# MD016A.net
KiCad netlist of a schematic drawn in Altium Designer
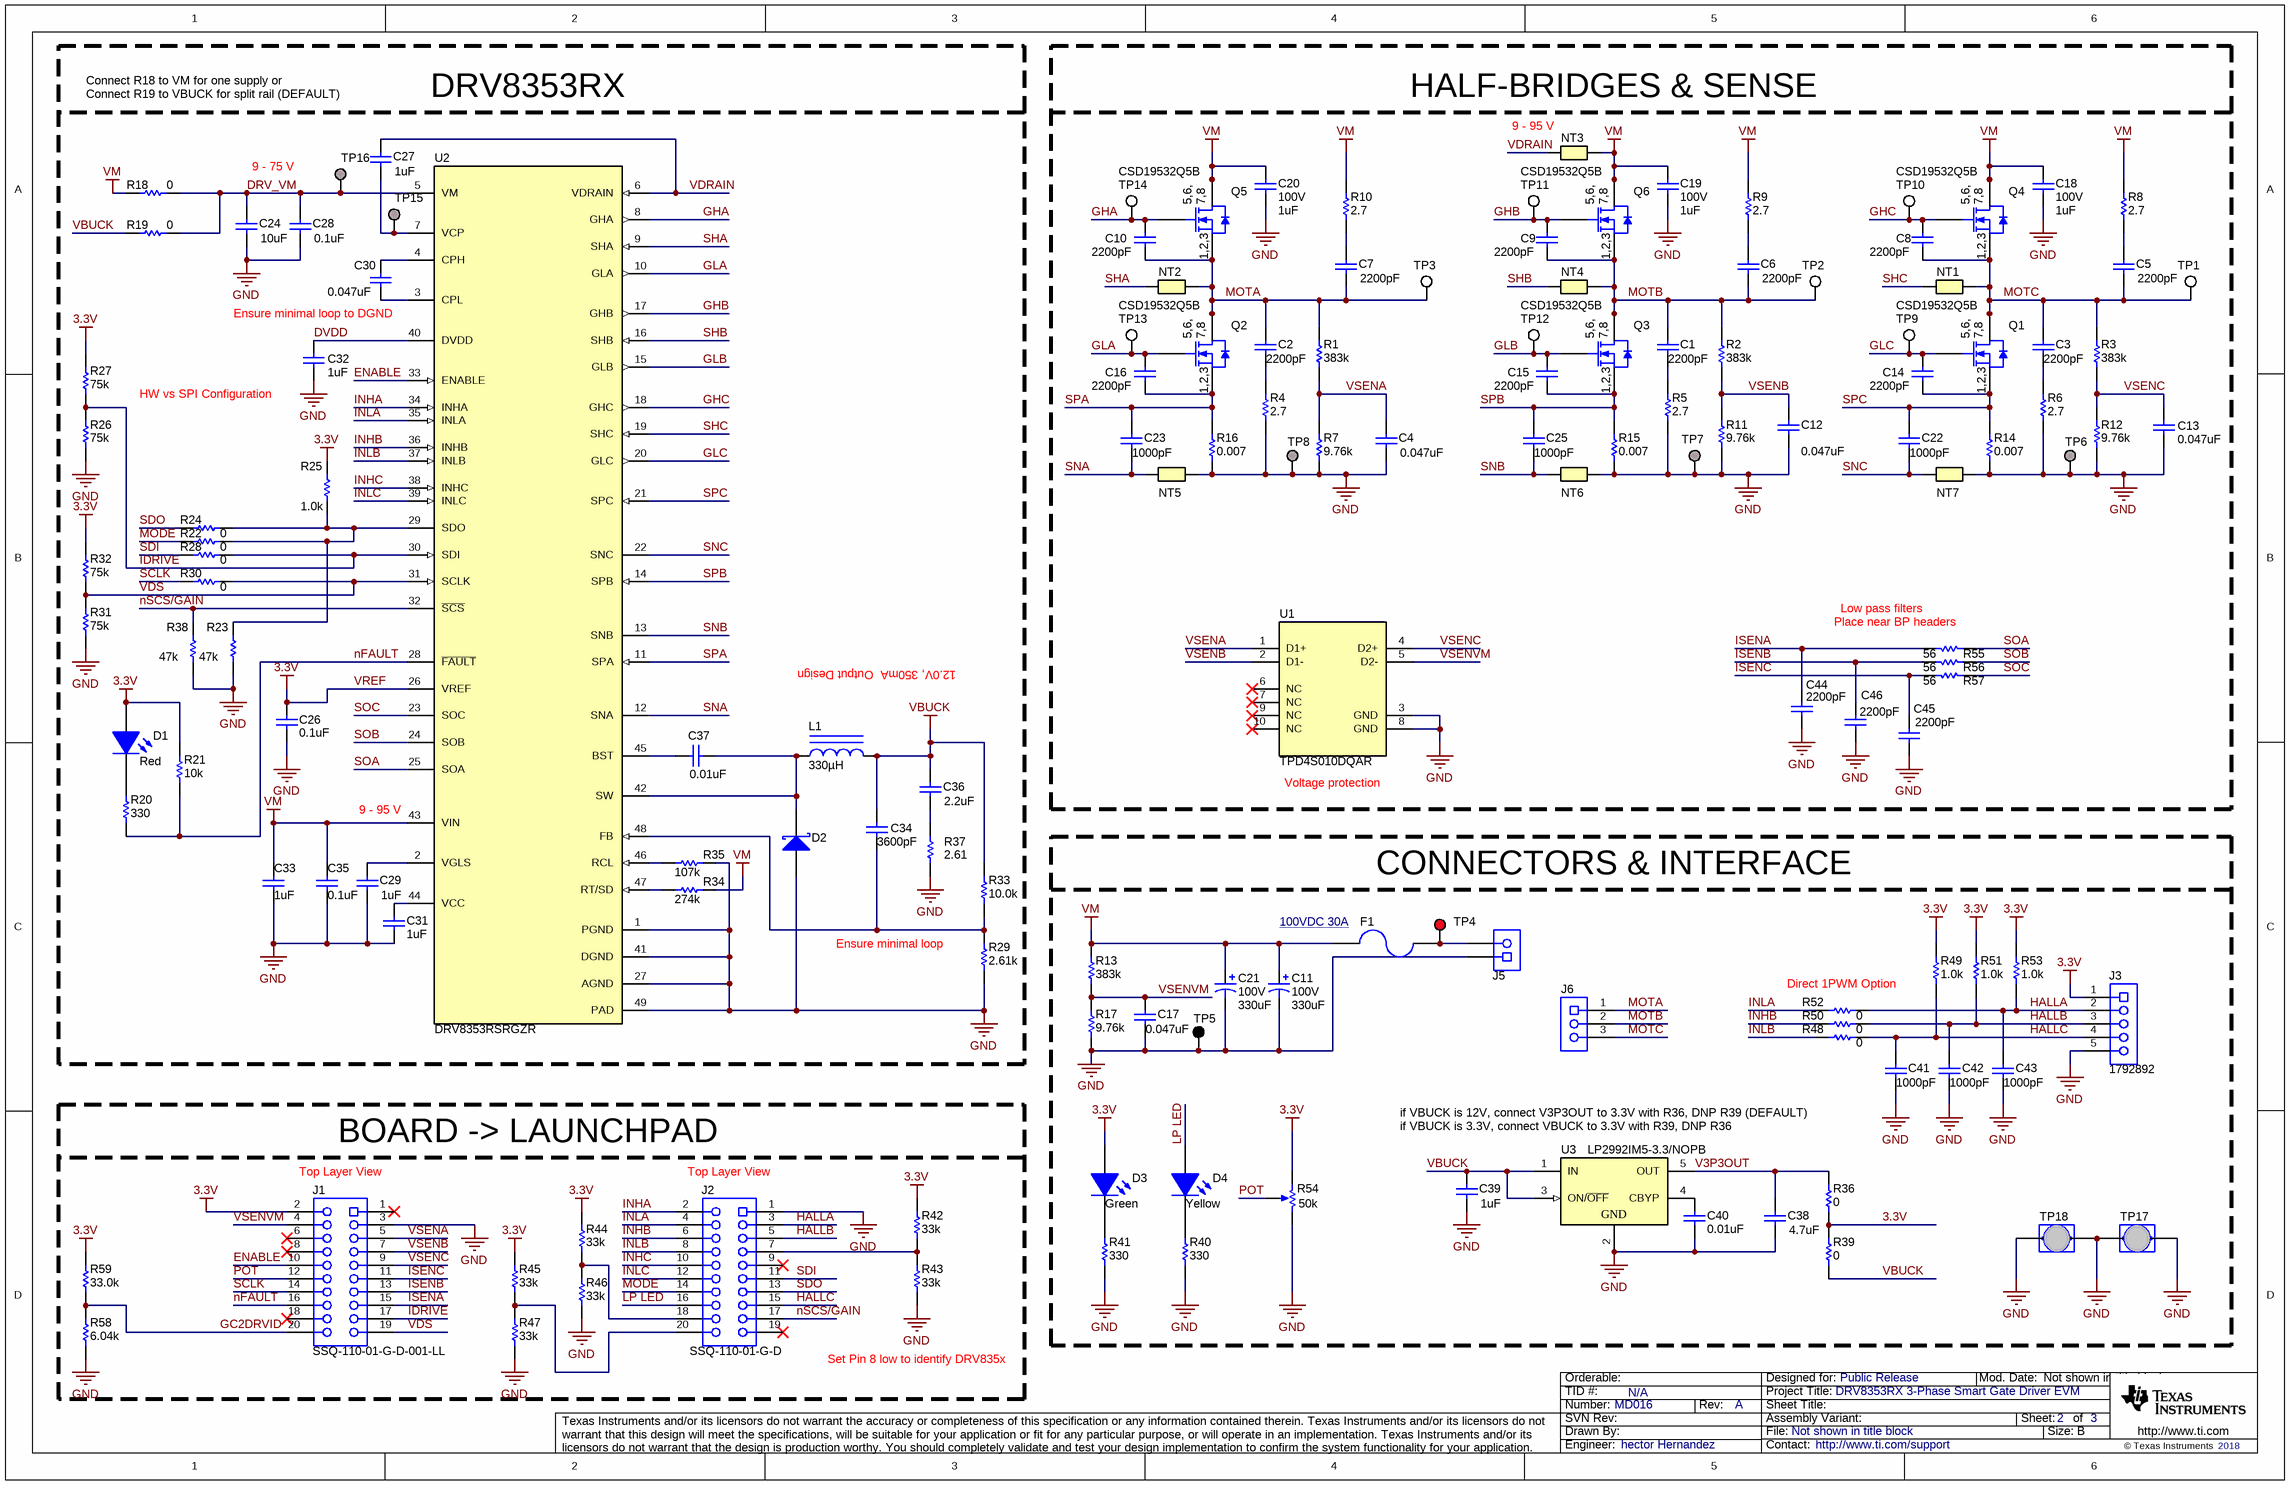
[diagram p0: MD016A.SchDoc]

(export (version "E")
  (design (tool "Eeschema 10.0.6"))
  (components
    (comp (ref "C1")
      (value "GRM188R72A222KA01D")
      (footprint "0603_HV")
      (description "CAP, CERM, 2200 pF, 100 V, +/- 10%, X7R, 0603")
      (fields
        (field (name "MANUFACTURER") "MuRata")
        (field (name "VALUEDISPLAYED") "2200pF")
        (field (name "PUBLISHER") "Texas Instruments")
      )
      (libsource (lib "Altium Vault - TI") (part "CMP-0007475-4"))
    )
    (comp (ref "C2")
      (value "GRM188R72A222KA01D")
      (footprint "0603_HV")
      (description "CAP, CERM, 2200 pF, 100 V, +/- 10%, X7R, 0603")
      (fields
        (field (name "MANUFACTURER") "MuRata")
        (field (name "VALUEDISPLAYED") "2200pF")
        (field (name "PUBLISHER") "Texas Instruments")
      )
      (libsource (lib "Altium Vault - TI") (part "CMP-0007475-4"))
    )
    (comp (ref "C3")
      (value "GRM188R72A222KA01D")
      (footprint "0603_HV")
      (description "CAP, CERM, 2200 pF, 100 V, +/- 10%, X7R, 0603")
      (fields
        (field (name "MANUFACTURER") "MuRata")
        (field (name "VALUEDISPLAYED") "2200pF")
        (field (name "PUBLISHER") "Texas Instruments")
      )
      (libsource (lib "Altium Vault - TI") (part "CMP-0007475-4"))
    )
    (comp (ref "C4")
      (value "06033C473JAT2A")
      (footprint "0603L")
      (description "CAP, CERM, 0.047 uF, 25 V, +/- 5%, X7R, 0603")
      (fields
        (field (name "MANUFACTURER") "AVX")
        (field (name "VALUEDISPLAYED") "0.047uF")
        (field (name "PUBLISHER") "Texas Instruments")
      )
      (libsource (lib "Altium Vault - TI") (part "CMP-0006757-5"))
    )
    (comp (ref "C5")
      (value "GRM188R72A222KA01D")
      (footprint "0603_HV")
      (description "CAP, CERM, 2200 pF, 100 V, +/- 10%, X7R, 0603")
      (fields
        (field (name "MANUFACTURER") "MuRata")
        (field (name "VALUEDISPLAYED") "2200pF")
        (field (name "PUBLISHER") "Texas Instruments")
      )
      (libsource (lib "Altium Vault - TI") (part "CMP-0007475-4"))
    )
    (comp (ref "C6")
      (value "GRM188R72A222KA01D")
      (footprint "0603_HV")
      (description "CAP, CERM, 2200 pF, 100 V, +/- 10%, X7R, 0603")
      (fields
        (field (name "MANUFACTURER") "MuRata")
        (field (name "VALUEDISPLAYED") "2200pF")
        (field (name "PUBLISHER") "Texas Instruments")
      )
      (libsource (lib "Altium Vault - TI") (part "CMP-0007475-4"))
    )
    (comp (ref "C7")
      (value "GRM188R72A222KA01D")
      (footprint "0603_HV")
      (description "CAP, CERM, 2200 pF, 100 V, +/- 10%, X7R, 0603")
      (fields
        (field (name "MANUFACTURER") "MuRata")
        (field (name "VALUEDISPLAYED") "2200pF")
        (field (name "PUBLISHER") "Texas Instruments")
      )
      (libsource (lib "Altium Vault - TI") (part "CMP-0007475-4"))
    )
    (comp (ref "C8")
      (value "06031C222KAT2A")
      (footprint "0603_HV")
      (description "CAP, CERM, 2200 pF, 100 V, +/- 10%, X7R, 0603")
      (fields
        (field (name "MANUFACTURER") "AVX")
        (field (name "VALUEDISPLAYED") "2200pF")
        (field (name "PUBLISHER") "Texas Instruments")
      )
      (libsource (lib "Altium Vault - TI") (part "CMP-0006737-4"))
    )
    (comp (ref "C9")
      (value "06031C222KAT2A")
      (footprint "0603_HV")
      (description "CAP, CERM, 2200 pF, 100 V, +/- 10%, X7R, 0603")
      (fields
        (field (name "MANUFACTURER") "AVX")
        (field (name "VALUEDISPLAYED") "2200pF")
        (field (name "PUBLISHER") "Texas Instruments")
      )
      (libsource (lib "Altium Vault - TI") (part "CMP-0006737-4"))
    )
    (comp (ref "C10")
      (value "06031C222KAT2A")
      (footprint "0603_HV")
      (description "CAP, CERM, 2200 pF, 100 V, +/- 10%, X7R, 0603")
      (fields
        (field (name "MANUFACTURER") "AVX")
        (field (name "VALUEDISPLAYED") "2200pF")
        (field (name "PUBLISHER") "Texas Instruments")
      )
      (libsource (lib "Altium Vault - TI") (part "CMP-0006737-4"))
    )
    (comp (ref "C11")
      (value "EEV-FK2A331M")
      (footprint "SM_RADIAL_K16")
      (description "CAP, AL, 330 uF, 100 V, +/- 20%, 0.153 ohm, AEC-Q200 Grade 2, SMD")
      (fields
        (field (name "MANUFACTURER") "Panasonic")
        (field (name "VDC_V") "100V")
        (field (name "VALUEDISPLAYED") "330uF")
        (field (name "PUBLISHER") "Texas Instruments")
      )
      (libsource (lib "Altium Vault - TI") (part "Cap_Polarized"))
    )
    (comp (ref "C12")
      (value "06033C473JAT2A")
      (footprint "0603L")
      (description "CAP, CERM, 0.047 uF, 25 V, +/- 5%, X7R, 0603")
      (fields
        (field (name "MANUFACTURER") "AVX")
        (field (name "VALUEDISPLAYED") "0.047uF")
        (field (name "PUBLISHER") "Texas Instruments")
      )
      (libsource (lib "Altium Vault - TI") (part "CMP-0006757-5"))
    )
    (comp (ref "C13")
      (value "06033C473JAT2A")
      (footprint "0603L")
      (description "CAP, CERM, 0.047 uF, 25 V, +/- 5%, X7R, 0603")
      (fields
        (field (name "MANUFACTURER") "AVX")
        (field (name "VALUEDISPLAYED") "0.047uF")
        (field (name "PUBLISHER") "Texas Instruments")
      )
      (libsource (lib "Altium Vault - TI") (part "CMP-0006757-5"))
    )
    (comp (ref "C14")
      (value "06031C222KAT2A")
      (footprint "0603_HV")
      (description "CAP, CERM, 2200 pF, 100 V, +/- 10%, X7R, 0603")
      (fields
        (field (name "MANUFACTURER") "AVX")
        (field (name "VALUEDISPLAYED") "2200pF")
        (field (name "PUBLISHER") "Texas Instruments")
      )
      (libsource (lib "Altium Vault - TI") (part "CMP-0006737-4"))
    )
    (comp (ref "C15")
      (value "06031C222KAT2A")
      (footprint "0603_HV")
      (description "CAP, CERM, 2200 pF, 100 V, +/- 10%, X7R, 0603")
      (fields
        (field (name "MANUFACTURER") "AVX")
        (field (name "VALUEDISPLAYED") "2200pF")
        (field (name "PUBLISHER") "Texas Instruments")
      )
      (libsource (lib "Altium Vault - TI") (part "CMP-0006737-4"))
    )
    (comp (ref "C16")
      (value "06031C222KAT2A")
      (footprint "0603_HV")
      (description "CAP, CERM, 2200 pF, 100 V, +/- 10%, X7R, 0603")
      (fields
        (field (name "MANUFACTURER") "AVX")
        (field (name "VALUEDISPLAYED") "2200pF")
        (field (name "PUBLISHER") "Texas Instruments")
      )
      (libsource (lib "Altium Vault - TI") (part "CMP-0006737-4"))
    )
    (comp (ref "C17")
      (value "06033C473JAT2A")
      (footprint "0603L")
      (description "CAP, CERM, 0.047 uF, 25 V, +/- 5%, X7R, 0603")
      (fields
        (field (name "MANUFACTURER") "AVX")
        (field (name "VALUEDISPLAYED") "0.047uF")
        (field (name "PUBLISHER") "Texas Instruments")
      )
      (libsource (lib "Altium Vault - TI") (part "CMP-0006757-5"))
    )
    (comp (ref "C18")
      (value "CL31B105KCHNNNE")
      (footprint "1206_180M")
      (description "CAP, CERM, 1 uF, 100 V, +/- 10%, X7R, 1206")
      (fields
        (field (name "MANUFACTURER") "Samsung")
        (field (name "VDC_V") "100V")
        (field (name "VALUEDISPLAYED") "1uF")
        (field (name "PUBLISHER") "Texas Instruments")
      )
      (libsource (lib "Altium Vault - TI") (part "CMP-0008801-2"))
    )
    (comp (ref "C19")
      (value "CL31B105KCHNNNE")
      (footprint "1206_180M")
      (description "CAP, CERM, 1 uF, 100 V, +/- 10%, X7R, 1206")
      (fields
        (field (name "MANUFACTURER") "Samsung")
        (field (name "VDC_V") "100V")
        (field (name "VALUEDISPLAYED") "1uF")
        (field (name "PUBLISHER") "Texas Instruments")
      )
      (libsource (lib "Altium Vault - TI") (part "CMP-0008801-2"))
    )
    (comp (ref "C20")
      (value "CL31B105KCHNNNE")
      (footprint "1206_180M")
      (description "CAP, CERM, 1 uF, 100 V, +/- 10%, X7R, 1206")
      (fields
        (field (name "MANUFACTURER") "Samsung")
        (field (name "VDC_V") "100V")
        (field (name "VALUEDISPLAYED") "1uF")
        (field (name "PUBLISHER") "Texas Instruments")
      )
      (libsource (lib "Altium Vault - TI") (part "CMP-0008801-2"))
    )
    (comp (ref "C21")
      (value "EEV-FK2A331M")
      (footprint "SM_RADIAL_K16")
      (description "CAP, AL, 330 uF, 100 V, +/- 20%, 0.153 ohm, AEC-Q200 Grade 2, SMD")
      (fields
        (field (name "MANUFACTURER") "Panasonic")
        (field (name "VDC_V") "100V")
        (field (name "VALUEDISPLAYED") "330uF")
        (field (name "PUBLISHER") "Texas Instruments")
      )
      (libsource (lib "Altium Vault - TI") (part "CMP-0011224-2"))
    )
    (comp (ref "C22")
      (value "885012206034")
      (footprint "0603L")
      (description "CAP, CERM, 1000 pF, 16 V, +/- 10%, X7R, 0603")
      (fields
        (field (name "MANUFACTURER") "Wurth Elektronik")
        (field (name "VALUEDISPLAYED") "1000pF")
        (field (name "PUBLISHER") "Texas Instruments")
      )
      (libsource (lib "Altium Vault - TI") (part "CMP-0006826-4"))
    )
    (comp (ref "C23")
      (value "885012206034")
      (footprint "0603L")
      (description "CAP, CERM, 1000 pF, 16 V, +/- 10%, X7R, 0603")
      (fields
        (field (name "MANUFACTURER") "Wurth Elektronik")
        (field (name "VALUEDISPLAYED") "1000pF")
        (field (name "PUBLISHER") "Texas Instruments")
      )
      (libsource (lib "Altium Vault - TI") (part "CMP-0006826-4"))
    )
    (comp (ref "C24")
      (value "CGA9N3X7S2A106K230KE")
      (footprint "2220_280M")
      (description "CAP, CERM, 10 uF, 100 V,+/- 10%, X7S, AEC-Q200 Grade 1, 2220")
      (fields
        (field (name "MANUFACTURER") "TDK")
        (field (name "VALUEDISPLAYED") "10uF")
        (field (name "PUBLISHER") "Texas Instruments")
      )
      (libsource (lib "Altium Vault - TI") (part "CMP-0064964-2"))
    )
    (comp (ref "C25")
      (value "885012206034")
      (footprint "0603L")
      (description "CAP, CERM, 1000 pF, 16 V, +/- 10%, X7R, 0603")
      (fields
        (field (name "MANUFACTURER") "Wurth Elektronik")
        (field (name "VALUEDISPLAYED") "1000pF")
        (field (name "PUBLISHER") "Texas Instruments")
      )
      (libsource (lib "Altium Vault - TI") (part "CMP-0006826-4"))
    )
    (comp (ref "C26")
      (value "C0603C104J4RACTU")
      (footprint "0603L")
      (description "CAP, CERM, 0.1 uF, 16 V, +/- 5%, X7R, 0603")
      (fields
        (field (name "VALUEDISPLAYED") "0.1uF")
        (field (name "MANUFACTURER") "Kemet")
        (field (name "PUBLISHER") "Texas Instruments")
      )
      (libsource (lib "Altium Vault - TI") (part "CMP-0006857-4"))
    )
    (comp (ref "C27")
      (value "CL31B105KCHNNNE")
      (footprint "1206_180M")
      (description "CAP, CERM, 1 uF, 100 V, +/- 10%, X7R, 1206")
      (fields
        (field (name "MANUFACTURER") "Samsung")
        (field (name "VALUEDISPLAYED") "1uF")
        (field (name "PUBLISHER") "Texas Instruments")
      )
      (libsource (lib "Altium Vault - TI") (part "CMP-0008801-2"))
    )
    (comp (ref "C28")
      (value "C2012X7R2A104K125AA")
      (footprint "0805_HV")
      (description "CAP, CERM, 0.1 uF, 100 V, +/- 10%, X7R, 0805")
      (fields
        (field (name "MANUFACTURER") "TDK")
        (field (name "VALUEDISPLAYED") "0.1uF")
        (field (name "PUBLISHER") "Texas Instruments")
      )
      (libsource (lib "Altium Vault - TI") (part "CMP-0007886-2"))
    )
    (comp (ref "C29")
      (value "C1608X7R1C105K080AC")
      (footprint "0603L")
      (description "CAP, CERM, 1 uF, 16 V, +/- 10%, X7R, 0603")
      (fields
        (field (name "MANUFACTURER") "TDK")
        (field (name "VALUEDISPLAYED") "1uF")
        (field (name "PUBLISHER") "Texas Instruments")
      )
      (libsource (lib "Altium Vault - TI") (part "CMP-0007037-4"))
    )
    (comp (ref "C30")
      (value "C2012X7R2A473K125AA")
      (footprint "0805_HV")
      (description "CAP, CERM, 0.047 uF, 100 V, +/- 10%, X7R, 0805")
      (fields
        (field (name "VALUEDISPLAYED") "0.047uF")
        (field (name "MANUFACTURER") "TDK")
        (field (name "PUBLISHER") "Texas Instruments")
      )
      (libsource (lib "Altium Vault - TI") (part "CMP-0007887-2"))
    )
    (comp (ref "C31")
      (value "C1608X7R1C105K080AC")
      (footprint "0603L")
      (description "CAP, CERM, 1 uF, 16 V, +/- 10%, X7R, 0603")
      (fields
        (field (name "MANUFACTURER") "TDK")
        (field (name "VALUEDISPLAYED") "1uF")
        (field (name "PUBLISHER") "Texas Instruments")
      )
      (libsource (lib "Altium Vault - TI") (part "CMP-0007037-4"))
    )
    (comp (ref "C32")
      (value "EMK107B7105KA-T")
      (footprint "0603L")
      (description "CAP, CERM, 1 uF, 16 V, +/- 10%, X7R, 0603")
      (fields
        (field (name "MANUFACTURER") "Taiyo Yuden")
        (field (name "VALUEDISPLAYED") "1uF")
        (field (name "PUBLISHER") "Texas Instruments")
      )
      (libsource (lib "Altium Vault - TI") (part "CMP-0007120-4"))
    )
    (comp (ref "C33")
      (value "CL31B105KCHNNNE")
      (footprint "1206_180M")
      (description "CAP, CERM, 1 uF, 100 V, +/- 10%, X7R, 1206")
      (fields
        (field (name "MANUFACTURER") "Samsung")
        (field (name "VALUEDISPLAYED") "1uF")
        (field (name "PUBLISHER") "Texas Instruments")
      )
      (libsource (lib "Altium Vault - TI") (part "CMP-0008801-2"))
    )
    (comp (ref "C34")
      (value "GRM1885C1H362JA01D")
      (footprint "0603L")
      (description "CAP, CERM, 3600 pF, 50 V, +/- 5%, C0G/NP0, 0603")
      (fields
        (field (name "MANUFACTURER") "MuRata")
        (field (name "VALUEDISPLAYED") "3600pF")
        (field (name "PUBLISHER") "Texas Instruments")
      )
      (libsource (lib "Altium Vault - TI") (part "CMP-0007213-4"))
    )
    (comp (ref "C35")
      (value "C2012X7R2A104K125AA")
      (footprint "0805_HV")
      (description "CAP, CERM, 0.1 uF, 100 V, +/- 10%, X7R, 0805")
      (fields
        (field (name "MANUFACTURER") "TDK")
        (field (name "VALUEDISPLAYED") "0.1uF")
        (field (name "PUBLISHER") "Texas Instruments")
      )
      (libsource (lib "Altium Vault - TI") (part "CMP-0007886-2"))
    )
    (comp (ref "C36")
      (value "C2012X7R1V225K085AC")
      (footprint "0805L")
      (description "CAP, CERM, 2.2 uF, 35 V, +/- 10%, X7R, 0805")
      (fields
        (field (name "MANUFACTURER") "TDK")
        (field (name "VALUEDISPLAYED") "2.2uF")
        (field (name "PUBLISHER") "Texas Instruments")
      )
      (libsource (lib "Altium Vault - TI") (part "CMP-0007883-2"))
    )
    (comp (ref "C37")
      (value "C0603C103K4RACTU")
      (footprint "0603L")
      (description "CAP, CERM, 0.01 uF, 16 V, +/- 10%, X7R, 0603")
      (fields
        (field (name "MANUFACTURER") "Kemet")
        (field (name "VALUEDISPLAYED") "0.01uF")
        (field (name "PUBLISHER") "Texas Instruments")
      )
      (libsource (lib "Altium Vault - TI") (part "CMP-0006853-4"))
    )
    (comp (ref "C38")
      (value "GRM32ER71K475KE14L")
      (footprint "1210_270L")
      (description "CAP, CERM, 4.7 uF, 80 V, +/- 10%, X7R, 1210")
      (fields
        (field (name "MANUFACTURER") "MuRata")
        (field (name "VALUEDISPLAYED") "4.7uF")
        (field (name "PUBLISHER") "Texas Instruments")
      )
      (libsource (lib "Altium Vault - TI") (part "CMP-0009230-2"))
    )
    (comp (ref "C39")
      (value "CL21B105KBFNNNE")
      (footprint "0805L")
      (description "CAP, CERM, 1 uF, 50 V, +/- 10%, X7R, 0805")
      (fields
        (field (name "MANUFACTURER") "Samsung Electro-Mechanics")
        (field (name "VALUEDISPLAYED") "1uF")
        (field (name "PUBLISHER") "Texas Instruments")
      )
      (libsource (lib "Altium Vault - TI") (part "CMP-0007994-2"))
    )
    (comp (ref "C40")
      (value "C0603C103K4RACTU")
      (footprint "0603L")
      (description "CAP, CERM, 0.01 uF, 16 V, +/- 10%, X7R, 0603")
      (fields
        (field (name "VALUEDISPLAYED") "0.01uF")
        (field (name "MANUFACTURER") "Kemet")
        (field (name "PUBLISHER") "Texas Instruments")
      )
      (libsource (lib "Altium Vault - TI") (part "Capacitor"))
    )
    (comp (ref "C41")
      (value "885012206034")
      (footprint "0603L")
      (description "CAP, CERM, 1000 pF, 16 V, +/- 10%, X7R, 0603")
      (fields
        (field (name "MANUFACTURER") "Wurth Elektronik")
        (field (name "VALUEDISPLAYED") "1000pF")
        (field (name "PUBLISHER") "Texas Instruments")
      )
      (libsource (lib "Altium Vault - TI") (part "CMP-0006826-4"))
    )
    (comp (ref "C42")
      (value "885012206034")
      (footprint "0603L")
      (description "CAP, CERM, 1000 pF, 16 V, +/- 10%, X7R, 0603")
      (fields
        (field (name "MANUFACTURER") "Wurth Elektronik")
        (field (name "VALUEDISPLAYED") "1000pF")
        (field (name "PUBLISHER") "Texas Instruments")
      )
      (libsource (lib "Altium Vault - TI") (part "CMP-0006826-4"))
    )
    (comp (ref "C43")
      (value "885012206034")
      (footprint "0603L")
      (description "CAP, CERM, 1000 pF, 16 V, +/- 10%, X7R, 0603")
      (fields
        (field (name "MANUFACTURER") "Wurth Elektronik")
        (field (name "VALUEDISPLAYED") "1000pF")
        (field (name "PUBLISHER") "Texas Instruments")
      )
      (libsource (lib "Altium Vault - TI") (part "CMP-0006826-4"))
    )
    (comp (ref "C44")
      (value "GRM188R71C222KA01D")
      (footprint "0603L")
      (description "CAP, CERM, 2200 pF, 16 V, +/- 10%, X7R, 0603")
      (fields
        (field (name "VALUEDISPLAYED") "2200pF")
        (field (name "MANUFACTURER") "MuRata")
        (field (name "PUBLISHER") "Texas Instruments")
      )
      (libsource (lib "Altium Vault - TI") (part "Capacitor"))
    )
    (comp (ref "C45")
      (value "GRM188R71C222KA01D")
      (footprint "0603L")
      (description "CAP, CERM, 2200 pF, 16 V, +/- 10%, X7R, 0603")
      (fields
        (field (name "VALUEDISPLAYED") "2200pF")
        (field (name "MANUFACTURER") "MuRata")
        (field (name "PUBLISHER") "Texas Instruments")
      )
      (libsource (lib "Altium Vault - TI") (part "Capacitor"))
    )
    (comp (ref "C46")
      (value "GRM188R71C222KA01D")
      (footprint "0603L")
      (description "CAP, CERM, 2200 pF, 16 V, +/- 10%, X7R, 0603")
      (fields
        (field (name "VALUEDISPLAYED") "2200pF")
        (field (name "MANUFACTURER") "MuRata")
        (field (name "PUBLISHER") "Texas Instruments")
      )
      (libsource (lib "Altium Vault - TI") (part "Capacitor"))
    )
    (comp (ref "D1")
      (value "Red")
      (footprint "LED_LTST-C170_Red")
      (description "LED, Red, SMD")
      (fields
        (field (name "MANUFACTURER") "Lite-On")
        (field (name "PARTNUMBER") "LTST-C170KRKT")
        (field (name "PUBLISHER") "Texas Instruments")
      )
      (libsource (lib "Altium Vault - TI") (part "LED"))
    )
    (comp (ref "D2")
      (value "DFLS1200-7")
      (footprint "PowerDI123")
      (description "Diode, Schottky, 200 V, 1 A, PowerDI123")
      (fields (field (name "MANUFACTURER") "Diodes Inc.") (field (name "PUBLISHER") "Texas Instruments"))
      (libsource (lib "Altium Vault - TI") (part "DIODE_SCHOTTKY"))
    )
    (comp (ref "D3")
      (value "Green")
      (footprint "LTST-C170KGKT_Green")
      (description "LED, Green, SMD")
      (fields
        (field (name "MANUFACTURER") "Lite-On")
        (field (name "PARTNUMBER") "LTST-C170KGKT")
        (field (name "PUBLISHER") "Texas Instruments")
      )
      (libsource (lib "Altium Vault - TI") (part "LED"))
    )
    (comp (ref "D4")
      (value "Yellow")
      (footprint "LED_LTST-C170")
      (description "LED, Yellow , SMD")
      (fields
        (field (name "MANUFACTURER") "Lite-On")
        (field (name "PARTNUMBER") "LTST-C170KSKT")
        (field (name "PUBLISHER") "Texas Instruments")
      )
      (libsource (lib "Altium Vault - TI") (part "LED"))
    )
    (comp (ref "F1")
      (value "100VDC 30A")
      (footprint "Fuse_0463")
      (description "Fuse, 30 A, 250 VAC, 100 VDC, SMD")
      (fields (field (name "PARTNUMBER") "0463030.ER") (field (name "MANUFACTURER") "Littelfuse"))
      (libsource (lib "Altium Vault - TI") (part "CMP-0077200-3"))
    )
    (comp (ref "J1")
      (value "SSQ-110-01-G-D-001-LL")
      (footprint "Samtec_SSQ-110-01-x-D-001-LL")
      (description "Receptacle, 2.54mm, 10x2, Gold, TH")
      (fields (field (name "MANUFACTURER") "Samtec"))
      (libsource (lib "Altium Vault - TI") (part "Receptacle_10x2"))
    )
    (comp (ref "J2")
      (value "SSQ-110-01-G-D")
      (footprint "Samtec_SSQ-110-01-x-D")
      (description "Receptacle, 2.54mm, 10x2, Gold, TH")
      (fields (field (name "MANUFACTURER") "Samtec"))
      (libsource (lib "Altium Vault - TI") (part "CMP-0082605-1"))
    )
    (comp (ref "J3")
      (value "1792892")
      (footprint "Phoenix_1792892")
      (description "Terminal Block, 5mm, 5x1, R/A, TH")
      (fields (field (name "MANUFACTURER") "Phoenix Contact") (field (name "PUBLISHER") "Texas Instruments"))
      (libsource (lib "Altium Vault - TI") (part "Receptacle_5x1"))
    )
    (comp (ref "J5")
      (value "1902547")
      (footprint "Phoenix_1902547")
      (description "Terminal Block, 9.52mm, 2x1, R/A, TH")
      (fields (field (name "MANUFACTURER") "Phoenix Contact") (field (name "PUBLISHER") "Texas Instruments"))
      (libsource (lib "Altium Vault - TI") (part "CMP-0055527-1"))
    )
    (comp (ref "J6")
      (value "1904150")
      (footprint "Phoenix_1904150")
      (description "Terminal Block, 9.52mm, 3x1, R/A, TH")
      (fields (field (name "MANUFACTURER") "Phoenix Contact") (field (name "PUBLISHER") "Texas Instruments"))
      (libsource (lib "Altium Vault - TI") (part "Receptacle_3x1"))
    )
    (comp (ref "L1")
      (value "74404084331")
      (footprint "WE-LQS_8040")
      (description "Inductor, Shielded, 330 µH, 0.66 A, 1.1245 ohm, SMD")
      (fields (field (name "MANUFACTURER") "Wurth Elektronik") (field (name "VALUEDISPLAYED") "330µH"))
      (libsource (lib "Altium Vault - TI") (part "Inductor_Iron"))
    )
    (comp (ref "NT1")
      (value "Net-Tie")
      (footprint "Net-Tie_10mil")
      (description "Single point connection between nets.")
      (libsource (lib "Altium Vault - TI") (part "Net-Tie"))
    )
    (comp (ref "NT2")
      (value "Net-Tie")
      (footprint "Net-Tie_10mil")
      (description "Single point connection between nets.")
      (libsource (lib "Altium Vault - TI") (part "Net-Tie"))
    )
    (comp (ref "NT3")
      (value "Net-Tie")
      (footprint "Net-Tie_50milWide_30milLong")
      (description "Single point connection between nets.")
      (libsource (lib "Altium Vault - TI") (part "Net-Tie"))
    )
    (comp (ref "NT4")
      (value "Net-Tie")
      (footprint "Net-Tie_10mil")
      (description "Single point connection between nets.")
      (libsource (lib "Altium Vault - TI") (part "Net-Tie"))
    )
    (comp (ref "NT5")
      (value "Net-Tie")
      (footprint "Net-Tie_10mil")
      (description "Single point connection between nets.")
      (libsource (lib "Altium Vault - TI") (part "Net-Tie"))
    )
    (comp (ref "NT6")
      (value "Net-Tie")
      (footprint "Net-Tie_10mil")
      (description "Single point connection between nets.")
      (libsource (lib "Altium Vault - TI") (part "Net-Tie"))
    )
    (comp (ref "NT7")
      (value "Net-Tie")
      (footprint "Net-Tie_10mil")
      (description "Single point connection between nets.")
      (libsource (lib "Altium Vault - TI") (part "Net-Tie"))
    )
    (comp (ref "Q1")
      (value "CSD19532Q5B")
      (footprint "DNK0008A")
      (description "MOSFET, N-CH, 100 V, 17 A, DNK0008A (VSON-CLIP-8)")
      (fields (field (name "MANUFACTURER") "Texas Instruments"))
      (libsource (lib "Altium Vault - TI") (part "MOSFET_N_D56789G4S123"))
    )
    (comp (ref "Q2")
      (value "CSD19532Q5B")
      (footprint "DNK0008A")
      (description "MOSFET, N-CH, 100 V, 17 A, DNK0008A (VSON-CLIP-8)")
      (fields (field (name "MANUFACTURER") "Texas Instruments"))
      (libsource (lib "Altium Vault - TI") (part "MOSFET_N_D56789G4S123"))
    )
    (comp (ref "Q3")
      (value "CSD19532Q5B")
      (footprint "DNK0008A")
      (description "MOSFET, N-CH, 100 V, 17 A, DNK0008A (VSON-CLIP-8)")
      (fields (field (name "MANUFACTURER") "Texas Instruments"))
      (libsource (lib "Altium Vault - TI") (part "MOSFET_N_D56789G4S123"))
    )
    (comp (ref "Q4")
      (value "CSD19532Q5B")
      (footprint "DNK0008A")
      (description "MOSFET, N-CH, 100 V, 17 A, DNK0008A (VSON-CLIP-8)")
      (fields (field (name "MANUFACTURER") "Texas Instruments"))
      (libsource (lib "Altium Vault - TI") (part "MOSFET_N_D56789G4S123"))
    )
    (comp (ref "Q5")
      (value "CSD19532Q5B")
      (footprint "DNK0008A")
      (description "MOSFET, N-CH, 100 V, 17 A, DNK0008A (VSON-CLIP-8)")
      (fields (field (name "MANUFACTURER") "Texas Instruments"))
      (libsource (lib "Altium Vault - TI") (part "MOSFET_N_D56789G4S123"))
    )
    (comp (ref "Q6")
      (value "CSD19532Q5B")
      (footprint "DNK0008A")
      (description "MOSFET, N-CH, 100 V, 17 A, DNK0008A (VSON-CLIP-8)")
      (fields (field (name "MANUFACTURER") "Texas Instruments"))
      (libsource (lib "Altium Vault - TI") (part "MOSFET_N_D56789G4S123"))
    )
    (comp (ref "R1")
      (value "CRCW0603383KFKEA")
      (footprint "0603_HV")
      (description "RES, 383 k, 1%, 0.1 W, AEC-Q200 Grade 0, 0603")
      (fields (field (name "MANUFACTURER") "Vishay-Dale") (field (name "VALUEDISPLAYED") "383k"))
      (libsource (lib "Altium Vault - TI") (part "CMP-0022362-4"))
    )
    (comp (ref "R2")
      (value "CRCW0603383KFKEA")
      (footprint "0603_HV")
      (description "RES, 383 k, 1%, 0.1 W, AEC-Q200 Grade 0, 0603")
      (fields (field (name "MANUFACTURER") "Vishay-Dale") (field (name "VALUEDISPLAYED") "383k"))
      (libsource (lib "Altium Vault - TI") (part "CMP-0022362-4"))
    )
    (comp (ref "R3")
      (value "CRCW0603383KFKEA")
      (footprint "0603_HV")
      (description "RES, 383 k, 1%, 0.1 W, AEC-Q200 Grade 0, 0603")
      (fields (field (name "MANUFACTURER") "Vishay-Dale") (field (name "VALUEDISPLAYED") "383k"))
      (libsource (lib "Altium Vault - TI") (part "CMP-0022362-4"))
    )
    (comp (ref "R4")
      (value "CRCW08052R70JNEA")
      (footprint "0805_HV")
      (description "RES, 2.7, 5%, 0.125 W, 0805")
      (fields
        (field (name "MANUFACTURER") "Vishay-Dale")
        (field (name "VALUEDISPLAYED") "2.7")
        (field (name "PUBLISHER") "Texas Instruments")
      )
      (libsource (lib "Altium Vault - TI") (part "CMP-0020521-2"))
    )
    (comp (ref "R5")
      (value "CRCW08052R70JNEA")
      (footprint "0805_HV")
      (description "RES, 2.7, 5%, 0.125 W, 0805")
      (fields
        (field (name "MANUFACTURER") "Vishay-Dale")
        (field (name "VALUEDISPLAYED") "2.7")
        (field (name "PUBLISHER") "Texas Instruments")
      )
      (libsource (lib "Altium Vault - TI") (part "CMP-0020521-2"))
    )
    (comp (ref "R6")
      (value "CRCW08052R70JNEA")
      (footprint "0805_HV")
      (description "RES, 2.7, 5%, 0.125 W, 0805")
      (fields
        (field (name "MANUFACTURER") "Vishay-Dale")
        (field (name "VALUEDISPLAYED") "2.7")
        (field (name "PUBLISHER") "Texas Instruments")
      )
      (libsource (lib "Altium Vault - TI") (part "CMP-0020521-2"))
    )
    (comp (ref "R7")
      (value "RC0603FR-079K76L")
      (footprint "0603L")
      (description "RES, 9.76 k, 1%, 0.1 W, 0603")
      (fields (field (name "MANUFACTURER") "Yageo") (field (name "VALUEDISPLAYED") "9.76k"))
      (libsource (lib "Altium Vault - TI") (part "CMP-0023336-5"))
    )
    (comp (ref "R8")
      (value "CRCW08052R70JNEA")
      (footprint "0805_HV")
      (description "RES, 2.7, 5%, 0.125 W, 0805")
      (fields
        (field (name "MANUFACTURER") "Vishay-Dale")
        (field (name "VALUEDISPLAYED") "2.7")
        (field (name "PUBLISHER") "Texas Instruments")
      )
      (libsource (lib "Altium Vault - TI") (part "CMP-0020521-2"))
    )
    (comp (ref "R9")
      (value "CRCW08052R70JNEA")
      (footprint "0805_HV")
      (description "RES, 2.7, 5%, 0.125 W, 0805")
      (fields
        (field (name "MANUFACTURER") "Vishay-Dale")
        (field (name "VALUEDISPLAYED") "2.7")
        (field (name "PUBLISHER") "Texas Instruments")
      )
      (libsource (lib "Altium Vault - TI") (part "CMP-0020521-2"))
    )
    (comp (ref "R10")
      (value "CRCW08052R70JNEA")
      (footprint "0805_HV")
      (description "RES, 2.7, 5%, 0.125 W, 0805")
      (fields
        (field (name "MANUFACTURER") "Vishay-Dale")
        (field (name "VALUEDISPLAYED") "2.7")
        (field (name "PUBLISHER") "Texas Instruments")
      )
      (libsource (lib "Altium Vault - TI") (part "CMP-0020521-2"))
    )
    (comp (ref "R11")
      (value "RC0603FR-079K76L")
      (footprint "0603L")
      (description "RES, 9.76 k, 1%, 0.1 W, 0603")
      (fields (field (name "MANUFACTURER") "Yageo") (field (name "VALUEDISPLAYED") "9.76k"))
      (libsource (lib "Altium Vault - TI") (part "CMP-0023336-5"))
    )
    (comp (ref "R12")
      (value "RC0603FR-079K76L")
      (footprint "0603L")
      (description "RES, 9.76 k, 1%, 0.1 W, 0603")
      (fields (field (name "MANUFACTURER") "Yageo") (field (name "VALUEDISPLAYED") "9.76k"))
      (libsource (lib "Altium Vault - TI") (part "CMP-0023336-5"))
    )
    (comp (ref "R13")
      (value "CRCW0603383KFKEA")
      (footprint "0603_HV")
      (description "RES, 383 k, 1%, 0.1 W, AEC-Q200 Grade 0, 0603")
      (fields (field (name "MANUFACTURER") "Vishay-Dale") (field (name "VALUEDISPLAYED") "383k"))
      (libsource (lib "Altium Vault - TI") (part "CMP-0022362-4"))
    )
    (comp (ref "R14")
      (value "CRE2512-FZ-R007E-3")
      (footprint "CRE2512-R5_R9")
      (description "RES, 0.007, 1%, 3 W, AEC-Q200 Grade 0, 2512")
      (fields
        (field (name "VALUEDISPLAYED") "0.007")
        (field (name "MANUFACTURER") "Bourns")
        (field (name "PUBLISHER") "Texas Instruments")
      )
      (libsource (lib "Altium Vault - TI") (part "Resistor"))
    )
    (comp (ref "R15")
      (value "CRE2512-FZ-R007E-3")
      (footprint "CRE2512-R5_R9")
      (description "RES, 0.007, 1%, 3 W, AEC-Q200 Grade 0, 2512")
      (fields
        (field (name "VALUEDISPLAYED") "0.007")
        (field (name "MANUFACTURER") "Bourns")
        (field (name "PUBLISHER") "Texas Instruments")
      )
      (libsource (lib "Altium Vault - TI") (part "Resistor"))
    )
    (comp (ref "R16")
      (value "CRE2512-FZ-R007E-3")
      (footprint "CRE2512-R5_R9")
      (description "RES, 0.007, 1%, 3 W, AEC-Q200 Grade 0, 2512")
      (fields
        (field (name "VALUEDISPLAYED") "0.007")
        (field (name "MANUFACTURER") "Bourns")
        (field (name "PUBLISHER") "Texas Instruments")
      )
      (libsource (lib "Altium Vault - TI") (part "Resistor"))
    )
    (comp (ref "R17")
      (value "RC0603FR-079K76L")
      (footprint "0603L")
      (description "RES, 9.76 k, 1%, 0.1 W, 0603")
      (fields (field (name "MANUFACTURER") "Yageo") (field (name "VALUEDISPLAYED") "9.76k"))
      (libsource (lib "Altium Vault - TI") (part "CMP-0023336-5"))
    )
    (comp (ref "R18")
      (value "RC1206JR-070RL")
      (footprint "1206")
      (description "RES, 0, 5%, 0.25 W, 1206")
      (fields
        (field (name "MANUFACTURER") "Yageo America")
        (field (name "VALUEDISPLAYED") "0")
        (field (name "PUBLISHER") "Texas Instruments")
      )
      (libsource (lib "Altium Vault - TI") (part "Resistor"))
    )
    (comp (ref "R19")
      (value "RC1206JR-070RL")
      (footprint "1206")
      (description "RES, 0, 5%, 0.25 W, 1206")
      (fields
        (field (name "MANUFACTURER") "Yageo America")
        (field (name "VALUEDISPLAYED") "0")
        (field (name "PUBLISHER") "Texas Instruments")
      )
      (libsource (lib "Altium Vault - TI") (part "Resistor"))
    )
    (comp (ref "R20")
      (value "CRCW0603330RJNEA")
      (footprint "0603L")
      (description "RES, 330, 5%, 0.1 W, AEC-Q200 Grade 0, 0603")
      (fields (field (name "MANUFACTURER") "Vishay-Dale") (field (name "VALUEDISPLAYED") "330"))
      (libsource (lib "Altium Vault - TI") (part "CMP-0025785-4"))
    )
    (comp (ref "R21")
      (value "RC0603JR-0710KL")
      (footprint "0603L")
      (description "RES, 10 k, 5%, 0.1 W, 0603")
      (fields
        (field (name "MANUFACTURER") "Yageo America")
        (field (name "VALUEDISPLAYED") "10k")
        (field (name "PUBLISHER") "Texas Instruments")
      )
      (libsource (lib "Altium Vault - TI") (part "CMP-0025886-3"))
    )
    (comp (ref "R22")
      (value "ERJ-3GEY0R00V")
      (footprint "0603L")
      (description "RES, 0, 5%, 0.1 W, 0603")
      (fields
        (field (name "MANUFACTURER") "Panasonic")
        (field (name "VALUEDISPLAYED") "0")
        (field (name "PUBLISHER") "Texas Instruments")
      )
      (libsource (lib "Altium Vault - TI") (part "CMP-0025874-3"))
    )
    (comp (ref "R23")
      (value "CRCW060347K0JNEA")
      (footprint "0603L")
      (description "RES, 47 k, 5%, 0.1 W, AEC-Q200 Grade 0, 0603")
      (fields (field (name "VALUEDISPLAYED") "47k") (field (name "MANUFACTURER") "Vishay-Dale"))
      (libsource (lib "Altium Vault - TI") (part "CMP-0025814-4"))
    )
    (comp (ref "R24")
      (value "ERJ-3GEY0R00V")
      (footprint "0603L")
      (description "RES, 0, 5%, 0.1 W, 0603")
      (fields
        (field (name "MANUFACTURER") "Panasonic")
        (field (name "VALUEDISPLAYED") "0")
        (field (name "PUBLISHER") "Texas Instruments")
      )
      (libsource (lib "Altium Vault - TI") (part "CMP-0025874-3"))
    )
    (comp (ref "R25")
      (value "RCA06031K00JNEA")
      (footprint "0603L")
      (description "RES, 1.0 k, 5%, 0.1 W, AEC-Q200 Grade 0, 0603")
      (fields
        (field (name "MANUFACTURER") "Vishay-Dale")
        (field (name "VALUEDISPLAYED") "1.0k")
        (field (name "PUBLISHER") "Texas Instruments")
      )
      (libsource (lib "Altium Vault - TI") (part "CMP-0025946-3"))
    )
    (comp (ref "R26")
      (value "CRCW060375K0JNEA")
      (footprint "0603L")
      (description "RES, 75 k, 5%, 0.1 W, AEC-Q200 Grade 0, 0603")
      (fields (field (name "VALUEDISPLAYED") "75k") (field (name "MANUFACTURER") "Vishay-Dale"))
      (libsource (lib "Altium Vault - TI") (part "CMP-0025853-4"))
    )
    (comp (ref "R27")
      (value "CRCW060375K0JNEA")
      (footprint "0603L")
      (description "RES, 75 k, 5%, 0.1 W, AEC-Q200 Grade 0, 0603")
      (fields (field (name "VALUEDISPLAYED") "75k") (field (name "MANUFACTURER") "Vishay-Dale"))
      (libsource (lib "Altium Vault - TI") (part "CMP-0025853-4"))
    )
    (comp (ref "R28")
      (value "ERJ-3GEY0R00V")
      (footprint "0603L")
      (description "RES, 0, 5%, 0.1 W, 0603")
      (fields
        (field (name "MANUFACTURER") "Panasonic")
        (field (name "VALUEDISPLAYED") "0")
        (field (name "PUBLISHER") "Texas Instruments")
      )
      (libsource (lib "Altium Vault - TI") (part "CMP-0025874-3"))
    )
    (comp (ref "R29")
      (value "RG1608P-2611-B-T5")
      (footprint "0603L")
      (description "RES, 2.61 k, 0.1%, 0.1 W, 0603")
      (fields
        (field (name "MANUFACTURER") "Susumu Co Ltd")
        (field (name "VALUEDISPLAYED") "2.61k")
        (field (name "PUBLISHER") "Texas Instruments")
      )
      (libsource (lib "Altium Vault - TI") (part "CMP-0023494-3"))
    )
    (comp (ref "R30")
      (value "ERJ-3GEY0R00V")
      (footprint "0603L")
      (description "RES, 0, 5%, 0.1 W, 0603")
      (fields
        (field (name "MANUFACTURER") "Panasonic")
        (field (name "VALUEDISPLAYED") "0")
        (field (name "PUBLISHER") "Texas Instruments")
      )
      (libsource (lib "Altium Vault - TI") (part "CMP-0025874-3"))
    )
    (comp (ref "R31")
      (value "CRCW060375K0JNEA")
      (footprint "0603L")
      (description "RES, 75 k, 5%, 0.1 W, AEC-Q200 Grade 0, 0603")
      (fields (field (name "VALUEDISPLAYED") "75k") (field (name "MANUFACTURER") "Vishay-Dale"))
      (libsource (lib "Altium Vault - TI") (part "CMP-0025853-4"))
    )
    (comp (ref "R32")
      (value "CRCW060375K0JNEA")
      (footprint "0603L")
      (description "RES, 75 k, 5%, 0.1 W, AEC-Q200 Grade 0, 0603")
      (fields (field (name "VALUEDISPLAYED") "75k") (field (name "MANUFACTURER") "Vishay-Dale"))
      (libsource (lib "Altium Vault - TI") (part "CMP-0025853-4"))
    )
    (comp (ref "R33")
      (value "RG1608P-103-B-T5")
      (footprint "0603L")
      (description "RES, 10.0 k, 0.1%, 0.1 W, 0603")
      (fields
        (field (name "MANUFACTURER") "Susumu Co Ltd")
        (field (name "VALUEDISPLAYED") "10.0k")
        (field (name "PUBLISHER") "Texas Instruments")
      )
      (libsource (lib "Altium Vault - TI") (part "CMP-0023404-3"))
    )
    (comp (ref "R34")
      (value "RC0603FR-07274KL")
      (footprint "0603_HV")
      (description "RES, 274 k, 1%, 0.1 W, 0603")
      (fields
        (field (name "MANUFACTURER") "Yageo America")
        (field (name "VALUEDISPLAYED") "274k")
        (field (name "PUBLISHER") "Texas Instruments")
      )
      (libsource (lib "Altium Vault - TI") (part "CMP-0022963-2"))
    )
    (comp (ref "R35")
      (value "RC0603FR-07107KL")
      (footprint "0603L")
      (description "RES, 107 k, 1%, 0.1 W, 0603")
      (fields
        (field (name "MANUFACTURER") "Yageo America")
        (field (name "VALUEDISPLAYED") "107k")
        (field (name "PUBLISHER") "Texas Instruments")
      )
      (libsource (lib "Altium Vault - TI") (part "CMP-0022741-2"))
    )
    (comp (ref "R36")
      (value "ERJ-3GEY0R00V")
      (footprint "0603L")
      (description "RES, 0, 5%, 0.1 W, 0603")
      (fields
        (field (name "MANUFACTURER") "Panasonic")
        (field (name "VALUEDISPLAYED") "0")
        (field (name "PUBLISHER") "Texas Instruments")
      )
      (libsource (lib "Altium Vault - TI") (part "CMP-0025874-3"))
    )
    (comp (ref "R37")
      (value "CRCW06032R61FKEA")
      (footprint "0603L")
      (description "RES, 2.61, 1%, 0.1 W, AEC-Q200 Grade 0, 0603")
      (fields (field (name "MANUFACTURER") "Vishay-Dale") (field (name "VALUEDISPLAYED") "2.61"))
      (libsource (lib "Altium Vault - TI") (part "CMP-0022313-4"))
    )
    (comp (ref "R38")
      (value "CRCW060347K0JNEA")
      (footprint "0603L")
      (description "RES, 47 k, 5%, 0.1 W, AEC-Q200 Grade 0, 0603")
      (fields (field (name "VALUEDISPLAYED") "47k") (field (name "MANUFACTURER") "Vishay-Dale"))
      (libsource (lib "Altium Vault - TI") (part "CMP-0025814-4"))
    )
    (comp (ref "R39")
      (value "ERJ-3GEY0R00V")
      (footprint "0603L")
      (description "RES, 0, 5%, 0.1 W, 0603")
      (fields
        (field (name "MANUFACTURER") "Panasonic")
        (field (name "VALUEDISPLAYED") "0")
        (field (name "PUBLISHER") "Texas Instruments")
      )
      (libsource (lib "Altium Vault - TI") (part "CMP-0025874-3"))
    )
    (comp (ref "R40")
      (value "CRCW0603330RJNEA")
      (footprint "0603L")
      (description "RES, 330, 5%, 0.1 W, AEC-Q200 Grade 0, 0603")
      (fields (field (name "MANUFACTURER") "Vishay-Dale") (field (name "VALUEDISPLAYED") "330"))
      (libsource (lib "Altium Vault - TI") (part "CMP-0025785-4"))
    )
    (comp (ref "R41")
      (value "CRCW0603330RJNEA")
      (footprint "0603L")
      (description "RES, 330, 5%, 0.1 W, AEC-Q200 Grade 0, 0603")
      (fields (field (name "MANUFACTURER") "Vishay-Dale") (field (name "VALUEDISPLAYED") "330"))
      (libsource (lib "Altium Vault - TI") (part "CMP-0025785-4"))
    )
    (comp (ref "R42")
      (value "Resistor")
      (footprint "0603L")
      (description "RES, 33 k, 5%, 0.1 W, AEC-Q200 Grade 0, 0603")
      (fields
        (field (name "PARTNUMBER") "CRCW060333K0JNEA")
        (field (name "VALUEDISPLAYED") "33k")
        (field (name "MANUFACTURER") "Vishay-Dale")
      )
      (libsource (lib "Altium Vault - TI") (part "CMP-0025786-4"))
    )
    (comp (ref "R43")
      (value "Resistor")
      (footprint "0603L")
      (description "RES, 33 k, 5%, 0.1 W, AEC-Q200 Grade 0, 0603")
      (fields
        (field (name "PARTNUMBER") "CRCW060333K0JNEA")
        (field (name "VALUEDISPLAYED") "33k")
        (field (name "MANUFACTURER") "Vishay-Dale")
      )
      (libsource (lib "Altium Vault - TI") (part "CMP-0025786-4"))
    )
    (comp (ref "R44")
      (value "Resistor")
      (footprint "0603L")
      (description "RES, 33 k, 5%, 0.1 W, AEC-Q200 Grade 0, 0603")
      (fields
        (field (name "PARTNUMBER") "CRCW060333K0JNEA")
        (field (name "VALUEDISPLAYED") "33k")
        (field (name "MANUFACTURER") "Vishay-Dale")
      )
      (libsource (lib "Altium Vault - TI") (part "Resistor"))
    )
    (comp (ref "R45")
      (value "Resistor")
      (footprint "0603L")
      (description "RES, 33 k, 5%, 0.1 W, AEC-Q200 Grade 0, 0603")
      (fields
        (field (name "PARTNUMBER") "CRCW060333K0JNEA")
        (field (name "VALUEDISPLAYED") "33k")
        (field (name "MANUFACTURER") "Vishay-Dale")
      )
      (libsource (lib "Altium Vault - TI") (part "Resistor"))
    )
    (comp (ref "R46")
      (value "Resistor")
      (footprint "0603L")
      (description "RES, 33 k, 5%, 0.1 W, AEC-Q200 Grade 0, 0603")
      (fields
        (field (name "PARTNUMBER") "CRCW060333K0JNEA")
        (field (name "VALUEDISPLAYED") "33k")
        (field (name "MANUFACTURER") "Vishay-Dale")
      )
      (libsource (lib "Altium Vault - TI") (part "Resistor"))
    )
    (comp (ref "R47")
      (value "Resistor")
      (footprint "0603L")
      (description "RES, 33 k, 5%, 0.1 W, AEC-Q200 Grade 0, 0603")
      (fields
        (field (name "PARTNUMBER") "CRCW060333K0JNEA")
        (field (name "VALUEDISPLAYED") "33k")
        (field (name "MANUFACTURER") "Vishay-Dale")
      )
      (libsource (lib "Altium Vault - TI") (part "Resistor"))
    )
    (comp (ref "R48")
      (value "ERJ-3GEY0R00V")
      (footprint "0603L")
      (description "RES, 0, 5%, 0.1 W, 0603")
      (fields
        (field (name "MANUFACTURER") "Panasonic")
        (field (name "VALUEDISPLAYED") "0")
        (field (name "PUBLISHER") "Texas Instruments")
      )
      (libsource (lib "Altium Vault - TI") (part "CMP-0025874-3"))
    )
    (comp (ref "R49")
      (value "RCA06031K00JNEA")
      (footprint "0603L")
      (description "RES, 1.0 k, 5%, 0.1 W, AEC-Q200 Grade 0, 0603")
      (fields
        (field (name "MANUFACTURER") "Vishay-Dale")
        (field (name "VALUEDISPLAYED") "1.0k")
        (field (name "PUBLISHER") "Texas Instruments")
      )
      (libsource (lib "Altium Vault - TI") (part "CMP-0025946-3"))
    )
    (comp (ref "R50")
      (value "ERJ-3GEY0R00V")
      (footprint "0603L")
      (description "RES, 0, 5%, 0.1 W, 0603")
      (fields
        (field (name "MANUFACTURER") "Panasonic")
        (field (name "VALUEDISPLAYED") "0")
        (field (name "PUBLISHER") "Texas Instruments")
      )
      (libsource (lib "Altium Vault - TI") (part "CMP-0025874-3"))
    )
    (comp (ref "R51")
      (value "RCA06031K00JNEA")
      (footprint "0603L")
      (description "RES, 1.0 k, 5%, 0.1 W, AEC-Q200 Grade 0, 0603")
      (fields
        (field (name "MANUFACTURER") "Vishay-Dale")
        (field (name "VALUEDISPLAYED") "1.0k")
        (field (name "PUBLISHER") "Texas Instruments")
      )
      (libsource (lib "Altium Vault - TI") (part "CMP-0025946-3"))
    )
    (comp (ref "R52")
      (value "ERJ-3GEY0R00V")
      (footprint "0603L")
      (description "RES, 0, 5%, 0.1 W, 0603")
      (fields
        (field (name "MANUFACTURER") "Panasonic")
        (field (name "VALUEDISPLAYED") "0")
        (field (name "PUBLISHER") "Texas Instruments")
      )
      (libsource (lib "Altium Vault - TI") (part "CMP-0025874-3"))
    )
    (comp (ref "R53")
      (value "RCA06031K00JNEA")
      (footprint "0603L")
      (description "RES, 1.0 k, 5%, 0.1 W, AEC-Q200 Grade 0, 0603")
      (fields
        (field (name "MANUFACTURER") "Vishay-Dale")
        (field (name "VALUEDISPLAYED") "1.0k")
        (field (name "PUBLISHER") "Texas Instruments")
      )
      (libsource (lib "Altium Vault - TI") (part "CMP-0025946-3"))
    )
    (comp (ref "R54")
      (value "50k")
      (footprint "Bourns_3352T")
      (description "Trimming Potentiometer, 50K, 0.5W, TH")
      (fields
        (field (name "PARTNUMBER") "3352T-1-503LF")
        (field (name "MANUFACTURER") "Bourns")
        (field (name "PUBLISHER") "Texas Instruments")
      )
      (libsource (lib "Altium Vault - TI") (part "Potentiometer"))
    )
    (comp (ref "R55")
      (value "56")
      (footprint "0603L")
      (description "RES, 56, 5%, 0.1 W, AEC-Q200 Grade 0, 0603")
      (fields (field (name "PARTNUMBER") "CRCW060356R0JNEA") (field (name "MANUFACTURER") "Vishay-Dale"))
      (libsource (lib "Altium Vault - TI") (part "Resistor"))
    )
    (comp (ref "R56")
      (value "56")
      (footprint "0603L")
      (description "RES, 56, 5%, 0.1 W, AEC-Q200 Grade 0, 0603")
      (fields (field (name "PARTNUMBER") "CRCW060356R0JNEA") (field (name "MANUFACTURER") "Vishay-Dale"))
      (libsource (lib "Altium Vault - TI") (part "Resistor"))
    )
    (comp (ref "R57")
      (value "56")
      (footprint "0603L")
      (description "RES, 56, 5%, 0.1 W, AEC-Q200 Grade 0, 0603")
      (fields (field (name "PARTNUMBER") "CRCW060356R0JNEA") (field (name "MANUFACTURER") "Vishay-Dale"))
      (libsource (lib "Altium Vault - TI") (part "Resistor"))
    )
    (comp (ref "R58")
      (value "RG1608P-6041-B-T5")
      (footprint "0603L")
      (description "RES, 6.04 k, 0.1%, 0.1 W, 0603")
      (fields
        (field (name "MANUFACTURER") "Susumu Co Ltd")
        (field (name "VALUEDISPLAYED") "6.04k")
        (field (name "PUBLISHER") "Texas Instruments")
      )
      (libsource (lib "Altium Vault - TI") (part "CMP-0023581-3"))
    )
    (comp (ref "R59")
      (value "MCT06030C3302FP500")
      (footprint "0603L")
      (description "RES, 33.0 k, 1%, 0.125 W, 0603")
      (fields
        (field (name "MANUFACTURER") "Vishay/Beyschlag")
        (field (name "VALUEDISPLAYED") "33.0k")
        (field (name "PUBLISHER") "Texas Instruments")
      )
      (libsource (lib "Altium Vault - TI") (part "CMP-0022734-3"))
    )
    (comp (ref "TP1")
      (value "5002")
      (footprint "Keystone5002")
      (description "Test Point, Miniature, White, TH")
      (fields (field (name "MANUFACTURER") "Keystone") (field (name "PUBLISHER") "Texas Instruments"))
      (libsource (lib "Altium Vault - TI") (part "5002"))
    )
    (comp (ref "TP2")
      (value "5002")
      (footprint "Keystone5002")
      (description "Test Point, Miniature, White, TH")
      (fields (field (name "MANUFACTURER") "Keystone") (field (name "PUBLISHER") "Texas Instruments"))
      (libsource (lib "Altium Vault - TI") (part "5002"))
    )
    (comp (ref "TP3")
      (value "5002")
      (footprint "Keystone5002")
      (description "Test Point, Miniature, White, TH")
      (fields (field (name "MANUFACTURER") "Keystone") (field (name "PUBLISHER") "Texas Instruments"))
      (libsource (lib "Altium Vault - TI") (part "5002"))
    )
    (comp (ref "TP4")
      (value "5000")
      (footprint "Keystone5000")
      (description "Test Point, Miniature, Red, TH")
      (fields (field (name "MANUFACTURER") "Keystone") (field (name "PUBLISHER") "Texas Instruments"))
      (libsource (lib "Altium Vault - TI") (part "5000"))
    )
    (comp (ref "TP5")
      (value "5001")
      (footprint "Keystone5001")
      (description "Test Point, Miniature, Black, TH")
      (fields (field (name "MANUFACTURER") "Keystone") (field (name "PUBLISHER") "Texas Instruments"))
      (libsource (lib "Altium Vault - TI") (part "5001"))
    )
    (comp (ref "TP6")
      (value "TP_SM_1MM")
      (footprint "TP_SM_1MM")
      (description "1mm Test Point, SMT")
      (fields (field (name "MANUFACTURER") "Any") (field (name "PUBLISHER") "Texas Instruments"))
      (libsource (lib "Altium Vault - TI") (part "TESTPOINT"))
    )
    (comp (ref "TP7")
      (value "TP_SM_1MM")
      (footprint "TP_SM_1MM")
      (description "1mm Test Point, SMT")
      (fields (field (name "MANUFACTURER") "Any") (field (name "PUBLISHER") "Texas Instruments"))
      (libsource (lib "Altium Vault - TI") (part "TESTPOINT"))
    )
    (comp (ref "TP8")
      (value "TP_SM_1MM")
      (footprint "TP_SM_1MM")
      (description "1mm Test Point, SMT")
      (fields (field (name "MANUFACTURER") "Any") (field (name "PUBLISHER") "Texas Instruments"))
      (libsource (lib "Altium Vault - TI") (part "TESTPOINT"))
    )
    (comp (ref "TP9")
      (value "5002")
      (footprint "Keystone5002")
      (description "Test Point, Miniature, White, TH")
      (fields (field (name "MANUFACTURER") "Keystone") (field (name "PUBLISHER") "Texas Instruments"))
      (libsource (lib "Altium Vault - TI") (part "5002"))
    )
    (comp (ref "TP10")
      (value "5002")
      (footprint "Keystone5002")
      (description "Test Point, Miniature, White, TH")
      (fields (field (name "MANUFACTURER") "Keystone") (field (name "PUBLISHER") "Texas Instruments"))
      (libsource (lib "Altium Vault - TI") (part "5002"))
    )
    (comp (ref "TP11")
      (value "5002")
      (footprint "Keystone5002")
      (description "Test Point, Miniature, White, TH")
      (fields (field (name "MANUFACTURER") "Keystone") (field (name "PUBLISHER") "Texas Instruments"))
      (libsource (lib "Altium Vault - TI") (part "5002"))
    )
    (comp (ref "TP12")
      (value "5002")
      (footprint "Keystone5002")
      (description "Test Point, Miniature, White, TH")
      (fields (field (name "MANUFACTURER") "Keystone") (field (name "PUBLISHER") "Texas Instruments"))
      (libsource (lib "Altium Vault - TI") (part "5002"))
    )
    (comp (ref "TP13")
      (value "5002")
      (footprint "Keystone5002")
      (description "Test Point, Miniature, White, TH")
      (fields (field (name "MANUFACTURER") "Keystone") (field (name "PUBLISHER") "Texas Instruments"))
      (libsource (lib "Altium Vault - TI") (part "5002"))
    )
    (comp (ref "TP14")
      (value "5002")
      (footprint "Keystone5002")
      (description "Test Point, Miniature, White, TH")
      (fields (field (name "MANUFACTURER") "Keystone") (field (name "PUBLISHER") "Texas Instruments"))
      (libsource (lib "Altium Vault - TI") (part "5002"))
    )
    (comp (ref "TP15")
      (value "TP_SM_1MM")
      (footprint "TP_SM_1MM")
      (description "1mm Test Point, SMT")
      (fields (field (name "MANUFACTURER") "Any") (field (name "PUBLISHER") "Texas Instruments"))
      (libsource (lib "Altium Vault - TI") (part "TESTPOINT"))
    )
    (comp (ref "TP16")
      (value "TP_SM_1MM")
      (footprint "TP_SM_1MM")
      (description "1mm Test Point, SMT")
      (fields (field (name "MANUFACTURER") "Any") (field (name "PUBLISHER") "Texas Instruments"))
      (libsource (lib "Altium Vault - TI") (part "TESTPOINT"))
    )
    (comp (ref "TP17")
      (value "D3082-05")
      (footprint "Harwin_D3082-05")
      (description "1mm Uninsulated Shorting Plug, 10.16mm spacing, TH")
      (fields (field (name "MANUFACTURER") "Harwin") (field (name "PUBLISHER") "Texas Instruments"))
      (libsource (lib "Altium Vault - TI") (part "Jumper_2p"))
    )
    (comp (ref "TP18")
      (value "D3082-05")
      (footprint "Harwin_D3082-05")
      (description "1mm Uninsulated Shorting Plug, 10.16mm spacing, TH")
      (fields (field (name "MANUFACTURER") "Harwin") (field (name "PUBLISHER") "Texas Instruments"))
      (libsource (lib "Altium Vault - TI") (part "Jumper_2p"))
    )
    (comp (ref "U1")
      (value "TPD4S010DQAR")
      (footprint "DQA0010A")
      (fields (field (name "MANUFACTURER") "Texas Instruments") (field (name "PARTNUMBER") "TPD4S010DQAR"))
      (libsource (lib "Altium Vault - TI") (part "TI-TPD4S010-SON_DQA-10"))
    )
    (comp (ref "U2")
      (value "DRV8353RSRGZR")
      (footprint "RGZ0048L")
      (description "100-V Three-Phase Smart Gate Driver, RGZ0048L (VQFN-48)")
      (fields
        (field (name "ALTERNATE PARTNUMBER") "DRV8353RSRGZT")
        (field (name "MANUFACTURER") "Texas Instruments")
        (field (name "PUBLISHER") "Texas Instruments")
      )
      (libsource (lib "Altium Vault - TI") (part "CMP-0013782-2"))
    )
    (comp (ref "U3")
      (value "LP2992IM5-3.3/NOPB")
      (footprint "DBV0005A_L")
      (description "Micropower 250 mA Low-Noise Ultra Low-Dropout Regulator, 5-pin SOT-23, Pb-Free")
      (fields (field (name "MANUFACTURER") "Texas Instruments"))
      (libsource (lib "Altium Vault - TI") (part "CMP-0071001-1"))
    )
  )
  (nets
    (net (code "1") (name "/DRV_VM") (class "Default")
      (node (ref "C24") (pin "1") (pinfunction "1_1") (pintype "passive"))
      (node (ref "C28") (pin "1") (pinfunction "1_1") (pintype "passive"))
      (node (ref "R18") (pin "2") (pinfunction "2_2") (pintype "passive"))
      (node (ref "R19") (pin "2") (pinfunction "2_2") (pintype "passive"))
      (node (ref "TP16") (pin "1") (pintype "passive"))
      (node (ref "U2") (pin "5") (pinfunction "VM_5") (pintype "power_in"))
    )
    (net (code "2") (name "/DVDD") (class "Default")
      (node (ref "C32") (pin "1") (pinfunction "1_1") (pintype "passive"))
      (node (ref "U2") (pin "40") (pinfunction "DVDD_40") (pintype "power_in"))
    )
    (net (code "3") (name "/ENABLE") (class "Default")
      (node (ref "J1") (pin "10") (pinfunction "10_10") (pintype "passive"))
      (node (ref "U2") (pin "33") (pinfunction "ENABLE_33") (pintype "input"))
    )
    (net (code "4") (name "/GC2DRVID") (class "Default")
      (node (ref "J1") (pin "20") (pinfunction "20_20") (pintype "passive"))
      (node (ref "R58") (pin "2") (pinfunction "2_2") (pintype "passive"))
      (node (ref "R59") (pin "1") (pinfunction "1_1") (pintype "passive"))
    )
    (net (code "5") (name "/GHA") (class "Default")
      (node (ref "C10") (pin "1") (pinfunction "1_1") (pintype "passive"))
      (node (ref "Q5") (pin "4") (pinfunction "G_4") (pintype "passive"))
      (node (ref "TP14") (pin "1") (pintype "passive"))
      (node (ref "U2") (pin "8") (pinfunction "GHA_8") (pintype "output"))
    )
    (net (code "6") (name "/GHB") (class "Default")
      (node (ref "C9") (pin "1") (pinfunction "1_1") (pintype "passive"))
      (node (ref "Q6") (pin "4") (pinfunction "G_4") (pintype "passive"))
      (node (ref "TP11") (pin "1") (pintype "passive"))
      (node (ref "U2") (pin "17") (pinfunction "GHB_17") (pintype "output"))
    )
    (net (code "7") (name "/GHC") (class "Default")
      (node (ref "C8") (pin "1") (pinfunction "1_1") (pintype "passive"))
      (node (ref "Q4") (pin "4") (pinfunction "G_4") (pintype "passive"))
      (node (ref "TP10") (pin "1") (pintype "passive"))
      (node (ref "U2") (pin "18") (pinfunction "GHC_18") (pintype "output"))
    )
    (net (code "8") (name "/GLA") (class "Default")
      (node (ref "C16") (pin "1") (pinfunction "1_1") (pintype "passive"))
      (node (ref "Q2") (pin "4") (pinfunction "G_4") (pintype "passive"))
      (node (ref "TP13") (pin "1") (pintype "passive"))
      (node (ref "U2") (pin "10") (pinfunction "GLA_10") (pintype "output"))
    )
    (net (code "9") (name "/GLB") (class "Default")
      (node (ref "C15") (pin "1") (pinfunction "1_1") (pintype "passive"))
      (node (ref "Q3") (pin "4") (pinfunction "G_4") (pintype "passive"))
      (node (ref "TP12") (pin "1") (pintype "passive"))
      (node (ref "U2") (pin "15") (pinfunction "GLB_15") (pintype "output"))
    )
    (net (code "10") (name "/GLC") (class "Default")
      (node (ref "C14") (pin "1") (pinfunction "1_1") (pintype "passive"))
      (node (ref "Q1") (pin "4") (pinfunction "G_4") (pintype "passive"))
      (node (ref "TP9") (pin "1") (pintype "passive"))
      (node (ref "U2") (pin "20") (pinfunction "GLC_20") (pintype "output"))
    )
    (net (code "11") (name "/HALLA") (class "Default")
      (node (ref "C43") (pin "1") (pinfunction "1_1") (pintype "passive"))
      (node (ref "J2") (pin "3") (pinfunction "3_3") (pintype "passive"))
      (node (ref "J3") (pin "2") (pinfunction "2_2") (pintype "passive"))
      (node (ref "R52") (pin "2") (pinfunction "2_2") (pintype "passive"))
      (node (ref "R53") (pin "1") (pinfunction "1_1") (pintype "passive"))
    )
    (net (code "12") (name "/HALLB") (class "Default")
      (node (ref "C42") (pin "1") (pinfunction "1_1") (pintype "passive"))
      (node (ref "J2") (pin "5") (pinfunction "5_5") (pintype "passive"))
      (node (ref "J3") (pin "3") (pinfunction "3_3") (pintype "passive"))
      (node (ref "R50") (pin "2") (pinfunction "2_2") (pintype "passive"))
      (node (ref "R51") (pin "1") (pinfunction "1_1") (pintype "passive"))
    )
    (net (code "13") (name "/HALLC") (class "Default")
      (node (ref "C41") (pin "1") (pinfunction "1_1") (pintype "passive"))
      (node (ref "J2") (pin "15") (pinfunction "15_15") (pintype "passive"))
      (node (ref "J3") (pin "4") (pinfunction "4_4") (pintype "passive"))
      (node (ref "R48") (pin "2") (pinfunction "2_2") (pintype "passive"))
      (node (ref "R49") (pin "1") (pinfunction "1_1") (pintype "passive"))
    )
    (net (code "14") (name "/IDRIVE") (class "Default")
      (node (ref "J1") (pin "17") (pinfunction "17_17") (pintype "passive"))
      (node (ref "R26") (pin "2") (pinfunction "2_2") (pintype "passive"))
      (node (ref "R27") (pin "1") (pinfunction "1_1") (pintype "passive"))
      (node (ref "R28") (pin "2") (pinfunction "2_2") (pintype "passive"))
      (node (ref "U2") (pin "30") (pinfunction "SDI_30") (pintype "input"))
    )
    (net (code "15") (name "/INHA") (class "Default")
      (node (ref "J2") (pin "2") (pinfunction "2_2") (pintype "passive"))
      (node (ref "U2") (pin "34") (pinfunction "INHA_34") (pintype "input"))
    )
    (net (code "16") (name "/INHB") (class "Default")
      (node (ref "J2") (pin "6") (pinfunction "6_6") (pintype "passive"))
      (node (ref "R50") (pin "1") (pinfunction "1_1") (pintype "passive"))
      (node (ref "U2") (pin "36") (pinfunction "INHB_36") (pintype "input"))
    )
    (net (code "17") (name "/INHC") (class "Default")
      (node (ref "J2") (pin "10") (pinfunction "10_10") (pintype "passive"))
      (node (ref "U2") (pin "38") (pinfunction "INHC_38") (pintype "input"))
    )
    (net (code "18") (name "/INLA") (class "Default")
      (node (ref "J2") (pin "4") (pinfunction "4_4") (pintype "passive"))
      (node (ref "R52") (pin "1") (pinfunction "1_1") (pintype "passive"))
      (node (ref "U2") (pin "35") (pinfunction "INLA_35") (pintype "input"))
    )
    (net (code "19") (name "/INLB") (class "Default")
      (node (ref "J2") (pin "8") (pinfunction "8_8") (pintype "passive"))
      (node (ref "R48") (pin "1") (pinfunction "1_1") (pintype "passive"))
      (node (ref "U2") (pin "37") (pinfunction "INLB_37") (pintype "input"))
    )
    (net (code "20") (name "/INLC") (class "Default")
      (node (ref "J2") (pin "12") (pinfunction "12_12") (pintype "passive"))
      (node (ref "U2") (pin "39") (pinfunction "INLC_39") (pintype "input"))
    )
    (net (code "21") (name "/ISENA") (class "Default")
      (node (ref "C44") (pin "1") (pinfunction "1_1") (pintype "passive"))
      (node (ref "J1") (pin "15") (pinfunction "15_15") (pintype "passive"))
      (node (ref "R55") (pin "2") (pinfunction "2_2") (pintype "passive"))
    )
    (net (code "22") (name "/ISENB") (class "Default")
      (node (ref "C46") (pin "1") (pinfunction "1_1") (pintype "passive"))
      (node (ref "J1") (pin "13") (pinfunction "13_13") (pintype "passive"))
      (node (ref "R56") (pin "2") (pinfunction "2_2") (pintype "passive"))
    )
    (net (code "23") (name "/ISENC") (class "Default")
      (node (ref "C45") (pin "1") (pinfunction "1_1") (pintype "passive"))
      (node (ref "J1") (pin "11") (pinfunction "11_11") (pintype "passive"))
      (node (ref "R57") (pin "2") (pinfunction "2_2") (pintype "passive"))
    )
    (net (code "24") (name "/LP LED") (class "Default")
      (node (ref "D4") (pin "1") (pinfunction "A_1") (pintype "passive"))
      (node (ref "J2") (pin "16") (pinfunction "16_16") (pintype "passive"))
    )
    (net (code "25") (name "/MODE") (class "Default")
      (node (ref "J2") (pin "14") (pinfunction "14_14") (pintype "passive"))
      (node (ref "R22") (pin "1") (pinfunction "1_1") (pintype "passive"))
    )
    (net (code "26") (name "/MOTA") (class "Default")
      (node (ref "C10") (pin "2") (pinfunction "2_2") (pintype "passive"))
      (node (ref "C2") (pin "1") (pinfunction "1_1") (pintype "passive"))
      (node (ref "C7") (pin "2") (pinfunction "2_2") (pintype "passive"))
      (node (ref "J6") (pin "1") (pinfunction "1_1") (pintype "passive"))
      (node (ref "NT2") (pin "2") (pinfunction "2_2") (pintype "passive"))
      (node (ref "Q2") (pin "5") (pinfunction "D_5") (pintype "passive"))
      (node (ref "Q2") (pin "6") (pinfunction "D_6") (pintype "passive"))
      (node (ref "Q2") (pin "7") (pinfunction "D_7") (pintype "passive"))
      (node (ref "Q2") (pin "8") (pinfunction "D_8") (pintype "passive"))
      (node (ref "Q2") (pin "9") (pinfunction "D_9") (pintype "passive"))
      (node (ref "Q5") (pin "1") (pinfunction "S_1") (pintype "passive"))
      (node (ref "Q5") (pin "2") (pinfunction "S_2") (pintype "passive"))
      (node (ref "Q5") (pin "3") (pinfunction "S_3") (pintype "passive"))
      (node (ref "R1") (pin "2") (pinfunction "2_2") (pintype "passive"))
      (node (ref "TP3") (pin "1") (pintype "passive"))
    )
    (net (code "27") (name "/MOTB") (class "Default")
      (node (ref "C1") (pin "1") (pinfunction "1_1") (pintype "passive"))
      (node (ref "C6") (pin "2") (pinfunction "2_2") (pintype "passive"))
      (node (ref "C9") (pin "2") (pinfunction "2_2") (pintype "passive"))
      (node (ref "J6") (pin "2") (pinfunction "2_2") (pintype "passive"))
      (node (ref "NT4") (pin "2") (pinfunction "2_2") (pintype "passive"))
      (node (ref "Q3") (pin "5") (pinfunction "D_5") (pintype "passive"))
      (node (ref "Q3") (pin "6") (pinfunction "D_6") (pintype "passive"))
      (node (ref "Q3") (pin "7") (pinfunction "D_7") (pintype "passive"))
      (node (ref "Q3") (pin "8") (pinfunction "D_8") (pintype "passive"))
      (node (ref "Q3") (pin "9") (pinfunction "D_9") (pintype "passive"))
      (node (ref "Q6") (pin "1") (pinfunction "S_1") (pintype "passive"))
      (node (ref "Q6") (pin "2") (pinfunction "S_2") (pintype "passive"))
      (node (ref "Q6") (pin "3") (pinfunction "S_3") (pintype "passive"))
      (node (ref "R2") (pin "2") (pinfunction "2_2") (pintype "passive"))
      (node (ref "TP2") (pin "1") (pintype "passive"))
    )
    (net (code "28") (name "/MOTC") (class "Default")
      (node (ref "C3") (pin "1") (pinfunction "1_1") (pintype "passive"))
      (node (ref "C5") (pin "2") (pinfunction "2_2") (pintype "passive"))
      (node (ref "C8") (pin "2") (pinfunction "2_2") (pintype "passive"))
      (node (ref "J6") (pin "3") (pinfunction "3_3") (pintype "passive"))
      (node (ref "NT1") (pin "2") (pinfunction "2_2") (pintype "passive"))
      (node (ref "Q1") (pin "5") (pinfunction "D_5") (pintype "passive"))
      (node (ref "Q1") (pin "6") (pinfunction "D_6") (pintype "passive"))
      (node (ref "Q1") (pin "7") (pinfunction "D_7") (pintype "passive"))
      (node (ref "Q1") (pin "8") (pinfunction "D_8") (pintype "passive"))
      (node (ref "Q1") (pin "9") (pinfunction "D_9") (pintype "passive"))
      (node (ref "Q4") (pin "1") (pinfunction "S_1") (pintype "passive"))
      (node (ref "Q4") (pin "2") (pinfunction "S_2") (pintype "passive"))
      (node (ref "Q4") (pin "3") (pinfunction "S_3") (pintype "passive"))
      (node (ref "R3") (pin "2") (pinfunction "2_2") (pintype "passive"))
      (node (ref "TP1") (pin "1") (pintype "passive"))
    )
    (net (code "29") (name "/POT") (class "Default")
      (node (ref "J1") (pin "12") (pinfunction "12_12") (pintype "passive"))
      (node (ref "R54") (pin "2") (pinfunction "WIPER_2") (pintype "passive"))
    )
    (net (code "30") (name "/SCLK") (class "Default")
      (node (ref "J1") (pin "14") (pinfunction "14_14") (pintype "passive"))
      (node (ref "R30") (pin "1") (pinfunction "1_1") (pintype "passive"))
    )
    (net (code "31") (name "/SDI") (class "Default")
      (node (ref "J2") (pin "11") (pinfunction "11_11") (pintype "passive"))
      (node (ref "R28") (pin "1") (pinfunction "1_1") (pintype "passive"))
    )
    (net (code "32") (name "/SDO") (class "Default")
      (node (ref "J2") (pin "13") (pinfunction "13_13") (pintype "passive"))
      (node (ref "R24") (pin "1") (pinfunction "1_1") (pintype "passive"))
    )
    (net (code "33") (name "/SHA") (class "Default")
      (node (ref "NT2") (pin "1") (pinfunction "1_1") (pintype "passive"))
      (node (ref "U2") (pin "9") (pinfunction "SHA_9") (pintype "input"))
    )
    (net (code "34") (name "/SHB") (class "Default")
      (node (ref "NT4") (pin "1") (pinfunction "1_1") (pintype "passive"))
      (node (ref "U2") (pin "16") (pinfunction "SHB_16") (pintype "input"))
    )
    (net (code "35") (name "/SHC") (class "Default")
      (node (ref "NT1") (pin "1") (pinfunction "1_1") (pintype "passive"))
      (node (ref "U2") (pin "19") (pinfunction "SHC_19") (pintype "input"))
    )
    (net (code "36") (name "/SNA") (class "Default")
      (node (ref "C23") (pin "2") (pinfunction "2_2") (pintype "passive"))
      (node (ref "NT5") (pin "1") (pinfunction "1_1") (pintype "passive"))
      (node (ref "U2") (pin "12") (pinfunction "SNA_12") (pintype "passive"))
    )
    (net (code "37") (name "/SNB") (class "Default")
      (node (ref "C25") (pin "2") (pinfunction "2_2") (pintype "passive"))
      (node (ref "NT6") (pin "1") (pinfunction "1_1") (pintype "passive"))
      (node (ref "U2") (pin "13") (pinfunction "SNB_13") (pintype "passive"))
    )
    (net (code "38") (name "/SNC") (class "Default")
      (node (ref "C22") (pin "2") (pinfunction "2_2") (pintype "passive"))
      (node (ref "NT7") (pin "1") (pinfunction "1_1") (pintype "passive"))
      (node (ref "U2") (pin "22") (pinfunction "SNC_22") (pintype "passive"))
    )
    (net (code "39") (name "/SOA") (class "Default")
      (node (ref "R55") (pin "1") (pinfunction "1_1") (pintype "passive"))
      (node (ref "U2") (pin "25") (pinfunction "SOA_25") (pintype "passive"))
    )
    (net (code "40") (name "/SOB") (class "Default")
      (node (ref "R56") (pin "1") (pinfunction "1_1") (pintype "passive"))
      (node (ref "U2") (pin "24") (pinfunction "SOB_24") (pintype "passive"))
    )
    (net (code "41") (name "/SOC") (class "Default")
      (node (ref "R57") (pin "1") (pinfunction "1_1") (pintype "passive"))
      (node (ref "U2") (pin "23") (pinfunction "SOC_23") (pintype "passive"))
    )
    (net (code "42") (name "/SPA") (class "Default")
      (node (ref "C16") (pin "2") (pinfunction "2_2") (pintype "passive"))
      (node (ref "C23") (pin "1") (pinfunction "1_1") (pintype "passive"))
      (node (ref "Q2") (pin "1") (pinfunction "S_1") (pintype "passive"))
      (node (ref "Q2") (pin "2") (pinfunction "S_2") (pintype "passive"))
      (node (ref "Q2") (pin "3") (pinfunction "S_3") (pintype "passive"))
      (node (ref "R16") (pin "2") (pinfunction "2_2") (pintype "passive"))
      (node (ref "U2") (pin "11") (pinfunction "SPA_11") (pintype "input"))
    )
    (net (code "43") (name "/SPB") (class "Default")
      (node (ref "C15") (pin "2") (pinfunction "2_2") (pintype "passive"))
      (node (ref "C25") (pin "1") (pinfunction "1_1") (pintype "passive"))
      (node (ref "Q3") (pin "1") (pinfunction "S_1") (pintype "passive"))
      (node (ref "Q3") (pin "2") (pinfunction "S_2") (pintype "passive"))
      (node (ref "Q3") (pin "3") (pinfunction "S_3") (pintype "passive"))
      (node (ref "R15") (pin "2") (pinfunction "2_2") (pintype "passive"))
      (node (ref "U2") (pin "14") (pinfunction "SPB_14") (pintype "input"))
    )
    (net (code "44") (name "/SPC") (class "Default")
      (node (ref "C14") (pin "2") (pinfunction "2_2") (pintype "passive"))
      (node (ref "C22") (pin "1") (pinfunction "1_1") (pintype "passive"))
      (node (ref "Q1") (pin "1") (pinfunction "S_1") (pintype "passive"))
      (node (ref "Q1") (pin "2") (pinfunction "S_2") (pintype "passive"))
      (node (ref "Q1") (pin "3") (pinfunction "S_3") (pintype "passive"))
      (node (ref "R14") (pin "2") (pinfunction "2_2") (pintype "passive"))
      (node (ref "U2") (pin "21") (pinfunction "SPC_21") (pintype "input"))
    )
    (net (code "45") (name "/V3P3OUT") (class "Default")
      (node (ref "C38") (pin "1") (pinfunction "1_1") (pintype "passive"))
      (node (ref "R36") (pin "2") (pinfunction "2_2") (pintype "passive"))
      (node (ref "U3") (pin "5") (pinfunction "OUT_5") (pintype "power_in"))
    )
    (net (code "46") (name "/VDRAIN") (class "Default")
      (node (ref "C27") (pin "1") (pinfunction "1_1") (pintype "passive"))
      (node (ref "NT3") (pin "1") (pinfunction "1_1") (pintype "passive"))
      (node (ref "U2") (pin "6") (pinfunction "VDRAIN_6") (pintype "input"))
    )
    (net (code "47") (name "/VDS") (class "Default")
      (node (ref "J1") (pin "19") (pinfunction "19_19") (pintype "passive"))
      (node (ref "R30") (pin "2") (pinfunction "2_2") (pintype "passive"))
      (node (ref "R31") (pin "2") (pinfunction "2_2") (pintype "passive"))
      (node (ref "R32") (pin "1") (pinfunction "1_1") (pintype "passive"))
      (node (ref "U2") (pin "31") (pinfunction "SCLK_31") (pintype "input"))
    )
    (net (code "48") (name "/VSENA") (class "Default")
      (node (ref "C4") (pin "1") (pinfunction "1_1") (pintype "passive"))
      (node (ref "J1") (pin "5") (pinfunction "5_5") (pintype "passive"))
      (node (ref "R1") (pin "1") (pinfunction "1_1") (pintype "passive"))
      (node (ref "R7") (pin "2") (pinfunction "2_2") (pintype "passive"))
      (node (ref "U1") (pin "1") (pinfunction "D1+_1") (pintype "passive"))
    )
    (net (code "49") (name "/VSENB") (class "Default")
      (node (ref "C12") (pin "1") (pinfunction "1_1") (pintype "passive"))
      (node (ref "J1") (pin "7") (pinfunction "7_7") (pintype "passive"))
      (node (ref "R11") (pin "2") (pinfunction "2_2") (pintype "passive"))
      (node (ref "R2") (pin "1") (pinfunction "1_1") (pintype "passive"))
      (node (ref "U1") (pin "2") (pinfunction "D1-_2") (pintype "passive"))
    )
    (net (code "50") (name "/VSENC") (class "Default")
      (node (ref "C13") (pin "1") (pinfunction "1_1") (pintype "passive"))
      (node (ref "J1") (pin "9") (pinfunction "9_9") (pintype "passive"))
      (node (ref "R12") (pin "2") (pinfunction "2_2") (pintype "passive"))
      (node (ref "R3") (pin "1") (pinfunction "1_1") (pintype "passive"))
      (node (ref "U1") (pin "4") (pinfunction "D2+_4") (pintype "passive"))
    )
    (net (code "51") (name "/VSENVM") (class "Default")
      (node (ref "C17") (pin "1") (pinfunction "1_1") (pintype "passive"))
      (node (ref "J1") (pin "4") (pinfunction "4_4") (pintype "passive"))
      (node (ref "R13") (pin "1") (pinfunction "1_1") (pintype "passive"))
      (node (ref "R17") (pin "2") (pinfunction "2_2") (pintype "passive"))
      (node (ref "U1") (pin "5") (pinfunction "D2-_5") (pintype "passive"))
    )
    (net (code "52") (name "/nFAULT") (class "Default")
      (node (ref "J1") (pin "16") (pinfunction "16_16") (pintype "passive"))
      (node (ref "R20") (pin "1") (pinfunction "1_1") (pintype "passive"))
      (node (ref "R21") (pin "1") (pinfunction "1_1") (pintype "passive"))
      (node (ref "U2") (pin "28") (pinfunction "FAULT_28") (pintype "open_collector"))
    )
    (net (code "53") (name "/nSCS{slash}GAIN") (class "Default")
      (node (ref "J2") (pin "17") (pinfunction "17_17") (pintype "passive"))
      (node (ref "R38") (pin "1") (pinfunction "1_1") (pintype "passive"))
      (node (ref "U2") (pin "32") (pinfunction "SCS_32") (pintype "passive"))
    )
    (net (code "54") (name "3.3V") (class "Default")
      (node (ref "C26") (pin "1") (pinfunction "1_1") (pintype "passive"))
      (node (ref "D1") (pin "1") (pinfunction "A_1") (pintype "passive"))
      (node (ref "D3") (pin "1") (pinfunction "A_1") (pintype "passive"))
      (node (ref "J1") (pin "2") (pinfunction "2_2") (pintype "passive"))
      (node (ref "J3") (pin "1") (pinfunction "1_1") (pintype "passive"))
      (node (ref "R21") (pin "2") (pinfunction "2_2") (pintype "passive"))
      (node (ref "R25") (pin "2") (pinfunction "2_2") (pintype "passive"))
      (node (ref "R27") (pin "2") (pinfunction "2_2") (pintype "passive"))
      (node (ref "R32") (pin "2") (pinfunction "2_2") (pintype "passive"))
      (node (ref "R36") (pin "1") (pinfunction "1_1") (pintype "passive"))
      (node (ref "R39") (pin "2") (pinfunction "2_2") (pintype "passive"))
      (node (ref "R42") (pin "2") (pinfunction "2_2") (pintype "passive"))
      (node (ref "R44") (pin "2") (pinfunction "2_2") (pintype "passive"))
      (node (ref "R45") (pin "2") (pinfunction "2_2") (pintype "passive"))
      (node (ref "R49") (pin "2") (pinfunction "2_2") (pintype "passive"))
      (node (ref "R51") (pin "2") (pinfunction "2_2") (pintype "passive"))
      (node (ref "R53") (pin "2") (pinfunction "2_2") (pintype "passive"))
      (node (ref "R54") (pin "3") (pinfunction "CW_3") (pintype "passive"))
      (node (ref "R59") (pin "2") (pinfunction "2_2") (pintype "passive"))
      (node (ref "U2") (pin "26") (pinfunction "VREF_26") (pintype "passive"))
    )
    (net (code "55") (name "GND") (class "Default")
      (node (ref "C11") (pin "2") (pinfunction "-_2") (pintype "passive"))
      (node (ref "C12") (pin "2") (pinfunction "2_2") (pintype "passive"))
      (node (ref "C13") (pin "2") (pinfunction "2_2") (pintype "passive"))
      (node (ref "C17") (pin "2") (pinfunction "2_2") (pintype "passive"))
      (node (ref "C18") (pin "2") (pinfunction "2_2") (pintype "passive"))
      (node (ref "C19") (pin "2") (pinfunction "2_2") (pintype "passive"))
      (node (ref "C20") (pin "2") (pinfunction "2_2") (pintype "passive"))
      (node (ref "C21") (pin "2") (pinfunction "-_2") (pintype "passive"))
      (node (ref "C24") (pin "2") (pinfunction "2_2") (pintype "passive"))
      (node (ref "C26") (pin "2") (pinfunction "2_2") (pintype "passive"))
      (node (ref "C28") (pin "2") (pinfunction "2_2") (pintype "passive"))
      (node (ref "C29") (pin "2") (pinfunction "2_2") (pintype "passive"))
      (node (ref "C31") (pin "1") (pinfunction "1_1") (pintype "passive"))
      (node (ref "C32") (pin "2") (pinfunction "2_2") (pintype "passive"))
      (node (ref "C33") (pin "2") (pinfunction "2_2") (pintype "passive"))
      (node (ref "C35") (pin "2") (pinfunction "2_2") (pintype "passive"))
      (node (ref "C38") (pin "2") (pinfunction "2_2") (pintype "passive"))
      (node (ref "C39") (pin "2") (pinfunction "2_2") (pintype "passive"))
      (node (ref "C4") (pin "2") (pinfunction "2_2") (pintype "passive"))
      (node (ref "C40") (pin "2") (pinfunction "2_2") (pintype "passive"))
      (node (ref "C41") (pin "2") (pinfunction "2_2") (pintype "passive"))
      (node (ref "C42") (pin "2") (pinfunction "2_2") (pintype "passive"))
      (node (ref "C43") (pin "2") (pinfunction "2_2") (pintype "passive"))
      (node (ref "C44") (pin "2") (pinfunction "2_2") (pintype "passive"))
      (node (ref "C45") (pin "2") (pinfunction "2_2") (pintype "passive"))
      (node (ref "C46") (pin "2") (pinfunction "2_2") (pintype "passive"))
      (node (ref "D2") (pin "2") (pinfunction "A_2") (pintype "passive"))
      (node (ref "J1") (pin "3") (pinfunction "3_3") (pintype "passive"))
      (node (ref "J2") (pin "1") (pinfunction "1_1") (pintype "passive"))
      (node (ref "J3") (pin "5") (pinfunction "5_5") (pintype "passive"))
      (node (ref "J5") (pin "1") (pinfunction "1_1") (pintype "passive"))
      (node (ref "NT5") (pin "2") (pinfunction "2_2") (pintype "passive"))
      (node (ref "NT6") (pin "2") (pinfunction "2_2") (pintype "passive"))
      (node (ref "NT7") (pin "2") (pinfunction "2_2") (pintype "passive"))
      (node (ref "R11") (pin "1") (pinfunction "1_1") (pintype "passive"))
      (node (ref "R12") (pin "1") (pinfunction "1_1") (pintype "passive"))
      (node (ref "R14") (pin "1") (pinfunction "1_1") (pintype "passive"))
      (node (ref "R15") (pin "1") (pinfunction "1_1") (pintype "passive"))
      (node (ref "R16") (pin "1") (pinfunction "1_1") (pintype "passive"))
      (node (ref "R17") (pin "1") (pinfunction "1_1") (pintype "passive"))
      (node (ref "R23") (pin "2") (pinfunction "2_2") (pintype "passive"))
      (node (ref "R26") (pin "1") (pinfunction "1_1") (pintype "passive"))
      (node (ref "R29") (pin "1") (pinfunction "1_1") (pintype "passive"))
      (node (ref "R31") (pin "1") (pinfunction "1_1") (pintype "passive"))
      (node (ref "R35") (pin "2") (pinfunction "2_2") (pintype "passive"))
      (node (ref "R37") (pin "1") (pinfunction "1_1") (pintype "passive"))
      (node (ref "R38") (pin "2") (pinfunction "2_2") (pintype "passive"))
      (node (ref "R4") (pin "1") (pinfunction "1_1") (pintype "passive"))
      (node (ref "R40") (pin "1") (pinfunction "1_1") (pintype "passive"))
      (node (ref "R41") (pin "1") (pinfunction "1_1") (pintype "passive"))
      (node (ref "R43") (pin "1") (pinfunction "1_1") (pintype "passive"))
      (node (ref "R46") (pin "1") (pinfunction "1_1") (pintype "passive"))
      (node (ref "R47") (pin "1") (pinfunction "1_1") (pintype "passive"))
      (node (ref "R5") (pin "1") (pinfunction "1_1") (pintype "passive"))
      (node (ref "R54") (pin "1") (pinfunction "CCW_1") (pintype "passive"))
      (node (ref "R58") (pin "1") (pinfunction "1_1") (pintype "passive"))
      (node (ref "R6") (pin "1") (pinfunction "1_1") (pintype "passive"))
      (node (ref "R7") (pin "1") (pinfunction "1_1") (pintype "passive"))
      (node (ref "TP17") (pin "1") (pinfunction "1_1") (pintype "passive"))
      (node (ref "TP17") (pin "2") (pinfunction "2_2") (pintype "passive"))
      (node (ref "TP18") (pin "1") (pinfunction "1_1") (pintype "passive"))
      (node (ref "TP18") (pin "2") (pinfunction "2_2") (pintype "passive"))
      (node (ref "TP5") (pin "1") (pintype "passive"))
      (node (ref "TP6") (pin "1") (pintype "passive"))
      (node (ref "TP7") (pin "1") (pintype "passive"))
      (node (ref "TP8") (pin "1") (pintype "passive"))
      (node (ref "U1") (pin "3") (pinfunction "GND_3") (pintype "power_in"))
      (node (ref "U1") (pin "8") (pinfunction "GND_8") (pintype "power_in"))
      (node (ref "U2") (pin "1") (pinfunction "PGND_1") (pintype "power_in"))
      (node (ref "U2") (pin "27") (pinfunction "AGND_27") (pintype "power_in"))
      (node (ref "U2") (pin "41") (pinfunction "DGND_41") (pintype "power_in"))
      (node (ref "U2") (pin "49") (pinfunction "PAD_49") (pintype "power_in"))
      (node (ref "U3") (pin "2") (pinfunction "GND_2") (pintype "power_in"))
    )
    (net (code "56") (name "Net-(C1-Pad2)") (class "Default")
      (node (ref "C1") (pin "2") (pinfunction "2_2") (pintype "passive"))
      (node (ref "R5") (pin "2") (pinfunction "2_2") (pintype "passive"))
    )
    (net (code "57") (name "Net-(C2-Pad2)") (class "Default")
      (node (ref "C2") (pin "2") (pinfunction "2_2") (pintype "passive"))
      (node (ref "R4") (pin "2") (pinfunction "2_2") (pintype "passive"))
    )
    (net (code "58") (name "Net-(C3-Pad2)") (class "Default")
      (node (ref "C3") (pin "2") (pinfunction "2_2") (pintype "passive"))
      (node (ref "R6") (pin "2") (pinfunction "2_2") (pintype "passive"))
    )
    (net (code "59") (name "Net-(C5-Pad1)") (class "Default")
      (node (ref "C5") (pin "1") (pinfunction "1_1") (pintype "passive"))
      (node (ref "R8") (pin "1") (pinfunction "1_1") (pintype "passive"))
    )
    (net (code "60") (name "Net-(C6-Pad1)") (class "Default")
      (node (ref "C6") (pin "1") (pinfunction "1_1") (pintype "passive"))
      (node (ref "R9") (pin "1") (pinfunction "1_1") (pintype "passive"))
    )
    (net (code "61") (name "Net-(C7-Pad1)") (class "Default")
      (node (ref "C7") (pin "1") (pinfunction "1_1") (pintype "passive"))
      (node (ref "R10") (pin "1") (pinfunction "1_1") (pintype "passive"))
    )
    (net (code "62") (name "Net-(C36-Pad2)") (class "Default")
      (node (ref "C36") (pin "2") (pinfunction "2_2") (pintype "passive"))
      (node (ref "R37") (pin "2") (pinfunction "2_2") (pintype "passive"))
    )
    (net (code "63") (name "Net-(D1-K)") (class "Default")
      (node (ref "D1") (pin "2") (pinfunction "K_2") (pintype "passive"))
      (node (ref "R20") (pin "2") (pinfunction "2_2") (pintype "passive"))
    )
    (net (code "64") (name "Net-(D2-K)") (class "Default")
      (node (ref "C37") (pin "1") (pinfunction "1_1") (pintype "passive"))
      (node (ref "D2") (pin "1") (pinfunction "K_1") (pintype "passive"))
      (node (ref "L1") (pin "1") (pinfunction "1_1") (pintype "passive"))
      (node (ref "U2") (pin "42") (pinfunction "SW_42") (pintype "power_in"))
    )
    (net (code "65") (name "Net-(D3-K)") (class "Default")
      (node (ref "D3") (pin "2") (pinfunction "K_2") (pintype "passive"))
      (node (ref "R41") (pin "2") (pinfunction "2_2") (pintype "passive"))
    )
    (net (code "66") (name "Net-(D4-K)") (class "Default")
      (node (ref "D4") (pin "2") (pinfunction "K_2") (pintype "passive"))
      (node (ref "R40") (pin "2") (pinfunction "2_2") (pintype "passive"))
    )
    (net (code "67") (name "Net-(F1-Pad1)") (class "Default")
      (node (ref "F1") (pin "1") (pinfunction "1_1") (pintype "passive"))
      (node (ref "J5") (pin "2") (pinfunction "2_2") (pintype "passive"))
      (node (ref "TP4") (pin "1") (pintype "passive"))
    )
    (net (code "68") (name "Net-(J2-Pad7)") (class "Default")
      (node (ref "J2") (pin "7") (pinfunction "7_7") (pintype "passive"))
      (node (ref "R42") (pin "1") (pinfunction "1_1") (pintype "passive"))
      (node (ref "R43") (pin "2") (pinfunction "2_2") (pintype "passive"))
    )
    (net (code "69") (name "Net-(J2-Pad18)") (class "Default")
      (node (ref "J2") (pin "18") (pinfunction "18_18") (pintype "passive"))
      (node (ref "R44") (pin "1") (pinfunction "1_1") (pintype "passive"))
      (node (ref "R46") (pin "2") (pinfunction "2_2") (pintype "passive"))
    )
    (net (code "70") (name "Net-(J2-Pad20)") (class "Default")
      (node (ref "J2") (pin "20") (pinfunction "20_20") (pintype "passive"))
      (node (ref "R45") (pin "1") (pinfunction "1_1") (pintype "passive"))
      (node (ref "R47") (pin "2") (pinfunction "2_2") (pintype "passive"))
    )
    (net (code "71") (name "Net-(U2-BST)") (class "Default")
      (node (ref "C37") (pin "2") (pinfunction "2_2") (pintype "passive"))
      (node (ref "U2") (pin "45") (pinfunction "BST_45") (pintype "power_in"))
    )
    (net (code "72") (name "Net-(U2-CPH)") (class "Default")
      (node (ref "C30") (pin "1") (pinfunction "1_1") (pintype "passive"))
      (node (ref "U2") (pin "4") (pinfunction "CPH_4") (pintype "passive"))
    )
    (net (code "73") (name "Net-(U2-CPL)") (class "Default")
      (node (ref "C30") (pin "2") (pinfunction "2_2") (pintype "passive"))
      (node (ref "U2") (pin "3") (pinfunction "CPL_3") (pintype "passive"))
    )
    (net (code "74") (name "Net-(U2-FB)") (class "Default")
      (node (ref "C34") (pin "2") (pinfunction "2_2") (pintype "passive"))
      (node (ref "R29") (pin "2") (pinfunction "2_2") (pintype "passive"))
      (node (ref "R33") (pin "1") (pinfunction "1_1") (pintype "passive"))
      (node (ref "U2") (pin "48") (pinfunction "FB_48") (pintype "input"))
    )
    (net (code "75") (name "Net-(U2-RCL)") (class "Default")
      (node (ref "R35") (pin "1") (pinfunction "1_1") (pintype "passive"))
      (node (ref "U2") (pin "46") (pinfunction "RCL_46") (pintype "input"))
    )
    (net (code "76") (name "Net-(U2-RT{slash}SD)") (class "Default")
      (node (ref "R34") (pin "1") (pinfunction "1_1") (pintype "passive"))
      (node (ref "U2") (pin "47") (pinfunction "RT/SD_47") (pintype "input"))
    )
    (net (code "77") (name "Net-(U2-SDO)") (class "Default")
      (node (ref "R22") (pin "2") (pinfunction "2_2") (pintype "passive"))
      (node (ref "R23") (pin "1") (pinfunction "1_1") (pintype "passive"))
      (node (ref "R24") (pin "2") (pinfunction "2_2") (pintype "passive"))
      (node (ref "R25") (pin "1") (pinfunction "1_1") (pintype "passive"))
      (node (ref "U2") (pin "29") (pinfunction "SDO_29") (pintype "passive"))
    )
    (net (code "78") (name "Net-(U2-VCC)") (class "Default")
      (node (ref "C31") (pin "2") (pinfunction "2_2") (pintype "passive"))
      (node (ref "U2") (pin "44") (pinfunction "VCC_44") (pintype "power_in"))
    )
    (net (code "79") (name "Net-(U2-VCP)") (class "Default")
      (node (ref "C27") (pin "2") (pinfunction "2_2") (pintype "passive"))
      (node (ref "TP15") (pin "1") (pintype "passive"))
      (node (ref "U2") (pin "7") (pinfunction "VCP_7") (pintype "power_in"))
    )
    (net (code "80") (name "Net-(U2-VGLS)") (class "Default")
      (node (ref "C29") (pin "1") (pinfunction "1_1") (pintype "passive"))
      (node (ref "U2") (pin "2") (pinfunction "VGLS_2") (pintype "power_in"))
    )
    (net (code "81") (name "Net-(U3-CBYP)") (class "Default")
      (node (ref "C40") (pin "1") (pinfunction "1_1") (pintype "passive"))
      (node (ref "U3") (pin "4") (pinfunction "CBYP_4") (pintype "passive"))
    )
    (net (code "82") (name "VBUCK") (class "Default")
      (node (ref "C34") (pin "1") (pinfunction "1_1") (pintype "passive"))
      (node (ref "C36") (pin "1") (pinfunction "1_1") (pintype "passive"))
      (node (ref "C39") (pin "1") (pinfunction "1_1") (pintype "passive"))
      (node (ref "L1") (pin "2") (pinfunction "2_2") (pintype "passive"))
      (node (ref "R19") (pin "1") (pinfunction "1_1") (pintype "passive"))
      (node (ref "R33") (pin "2") (pinfunction "2_2") (pintype "passive"))
      (node (ref "R39") (pin "1") (pinfunction "1_1") (pintype "passive"))
      (node (ref "U3") (pin "1") (pinfunction "IN_1") (pintype "power_in"))
      (node (ref "U3") (pin "3") (pinfunction "ON/~{OFF}_3") (pintype "input"))
    )
    (net (code "83") (name "VM") (class "Default")
      (node (ref "C11") (pin "1") (pinfunction "+_1") (pintype "passive"))
      (node (ref "C18") (pin "1") (pinfunction "1_1") (pintype "passive"))
      (node (ref "C19") (pin "1") (pinfunction "1_1") (pintype "passive"))
      (node (ref "C20") (pin "1") (pinfunction "1_1") (pintype "passive"))
      (node (ref "C21") (pin "1") (pinfunction "+_1") (pintype "passive"))
      (node (ref "C33") (pin "1") (pinfunction "1_1") (pintype "passive"))
      (node (ref "C35") (pin "1") (pinfunction "1_1") (pintype "passive"))
      (node (ref "F1") (pin "2") (pinfunction "2_2") (pintype "passive"))
      (node (ref "NT3") (pin "2") (pinfunction "2_2") (pintype "passive"))
      (node (ref "Q4") (pin "5") (pinfunction "D_5") (pintype "passive"))
      (node (ref "Q4") (pin "6") (pinfunction "D_6") (pintype "passive"))
      (node (ref "Q4") (pin "7") (pinfunction "D_7") (pintype "passive"))
      (node (ref "Q4") (pin "8") (pinfunction "D_8") (pintype "passive"))
      (node (ref "Q4") (pin "9") (pinfunction "D_9") (pintype "passive"))
      (node (ref "Q5") (pin "5") (pinfunction "D_5") (pintype "passive"))
      (node (ref "Q5") (pin "6") (pinfunction "D_6") (pintype "passive"))
      (node (ref "Q5") (pin "7") (pinfunction "D_7") (pintype "passive"))
      (node (ref "Q5") (pin "8") (pinfunction "D_8") (pintype "passive"))
      (node (ref "Q5") (pin "9") (pinfunction "D_9") (pintype "passive"))
      (node (ref "Q6") (pin "5") (pinfunction "D_5") (pintype "passive"))
      (node (ref "Q6") (pin "6") (pinfunction "D_6") (pintype "passive"))
      (node (ref "Q6") (pin "7") (pinfunction "D_7") (pintype "passive"))
      (node (ref "Q6") (pin "8") (pinfunction "D_8") (pintype "passive"))
      (node (ref "Q6") (pin "9") (pinfunction "D_9") (pintype "passive"))
      (node (ref "R10") (pin "2") (pinfunction "2_2") (pintype "passive"))
      (node (ref "R13") (pin "2") (pinfunction "2_2") (pintype "passive"))
      (node (ref "R18") (pin "1") (pinfunction "1_1") (pintype "passive"))
      (node (ref "R34") (pin "2") (pinfunction "2_2") (pintype "passive"))
      (node (ref "R8") (pin "2") (pinfunction "2_2") (pintype "passive"))
      (node (ref "R9") (pin "2") (pinfunction "2_2") (pintype "passive"))
      (node (ref "U2") (pin "43") (pinfunction "VIN_43") (pintype "power_in"))
    )
    (net (code "84") (name "unconnected-(J1-Pad1)") (class "Default")
      (node (ref "J1") (pin "1") (pinfunction "1_1") (pintype "passive+no_connect"))
    )
    (net (code "85") (name "unconnected-(J1-Pad6)") (class "Default")
      (node (ref "J1") (pin "6") (pinfunction "6_6") (pintype "passive+no_connect"))
    )
    (net (code "86") (name "unconnected-(J1-Pad8)") (class "Default")
      (node (ref "J1") (pin "8") (pinfunction "8_8") (pintype "passive+no_connect"))
    )
    (net (code "87") (name "unconnected-(J1-Pad18)") (class "Default")
      (node (ref "J1") (pin "18") (pinfunction "18_18") (pintype "passive+no_connect"))
    )
    (net (code "88") (name "unconnected-(J2-Pad9)") (class "Default")
      (node (ref "J2") (pin "9") (pinfunction "9_9") (pintype "passive+no_connect"))
    )
    (net (code "89") (name "unconnected-(J2-Pad19)") (class "Default")
      (node (ref "J2") (pin "19") (pinfunction "19_19") (pintype "passive+no_connect"))
    )
    (net (code "90") (name "unconnected-(U1-NC-Pad6)") (class "Default")
      (node (ref "U1") (pin "6") (pinfunction "NC_6") (pintype "passive+no_connect"))
    )
    (net (code "91") (name "unconnected-(U1-NC-Pad7)") (class "Default")
      (node (ref "U1") (pin "7") (pinfunction "NC_7") (pintype "passive+no_connect"))
    )
    (net (code "92") (name "unconnected-(U1-NC-Pad9)") (class "Default")
      (node (ref "U1") (pin "9") (pinfunction "NC_9") (pintype "passive+no_connect"))
    )
    (net (code "93") (name "unconnected-(U1-NC-Pad10)") (class "Default")
      (node (ref "U1") (pin "10") (pinfunction "NC_10") (pintype "passive+no_connect"))
    )
  )
)
